# sensor_003.net
KiCad netlist of a schematic drawn in EAGLE
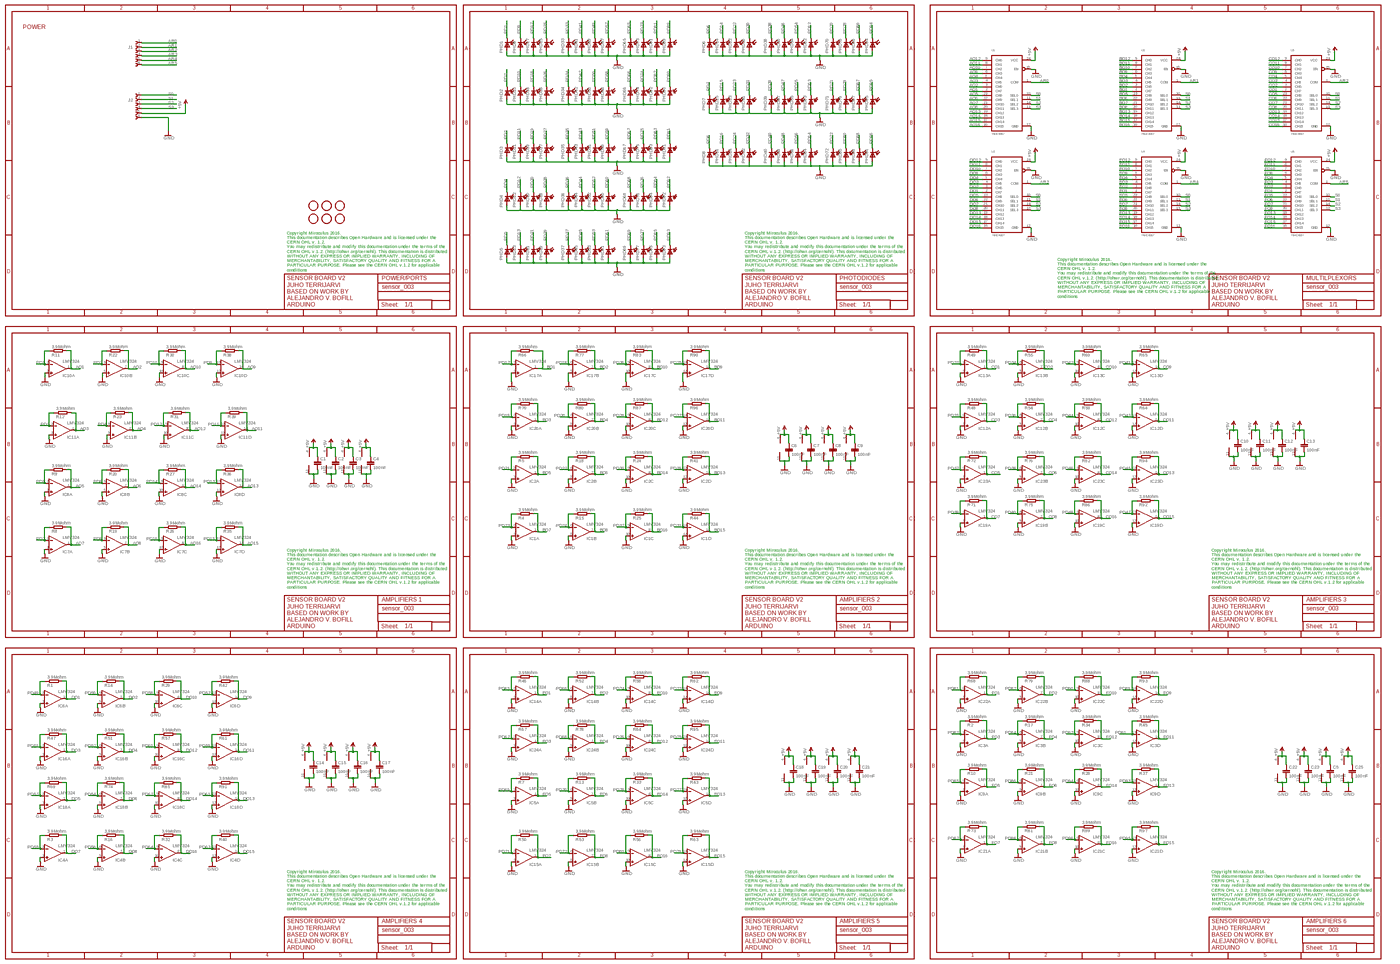
[diagram p0: schematic, sheet 1, overview]
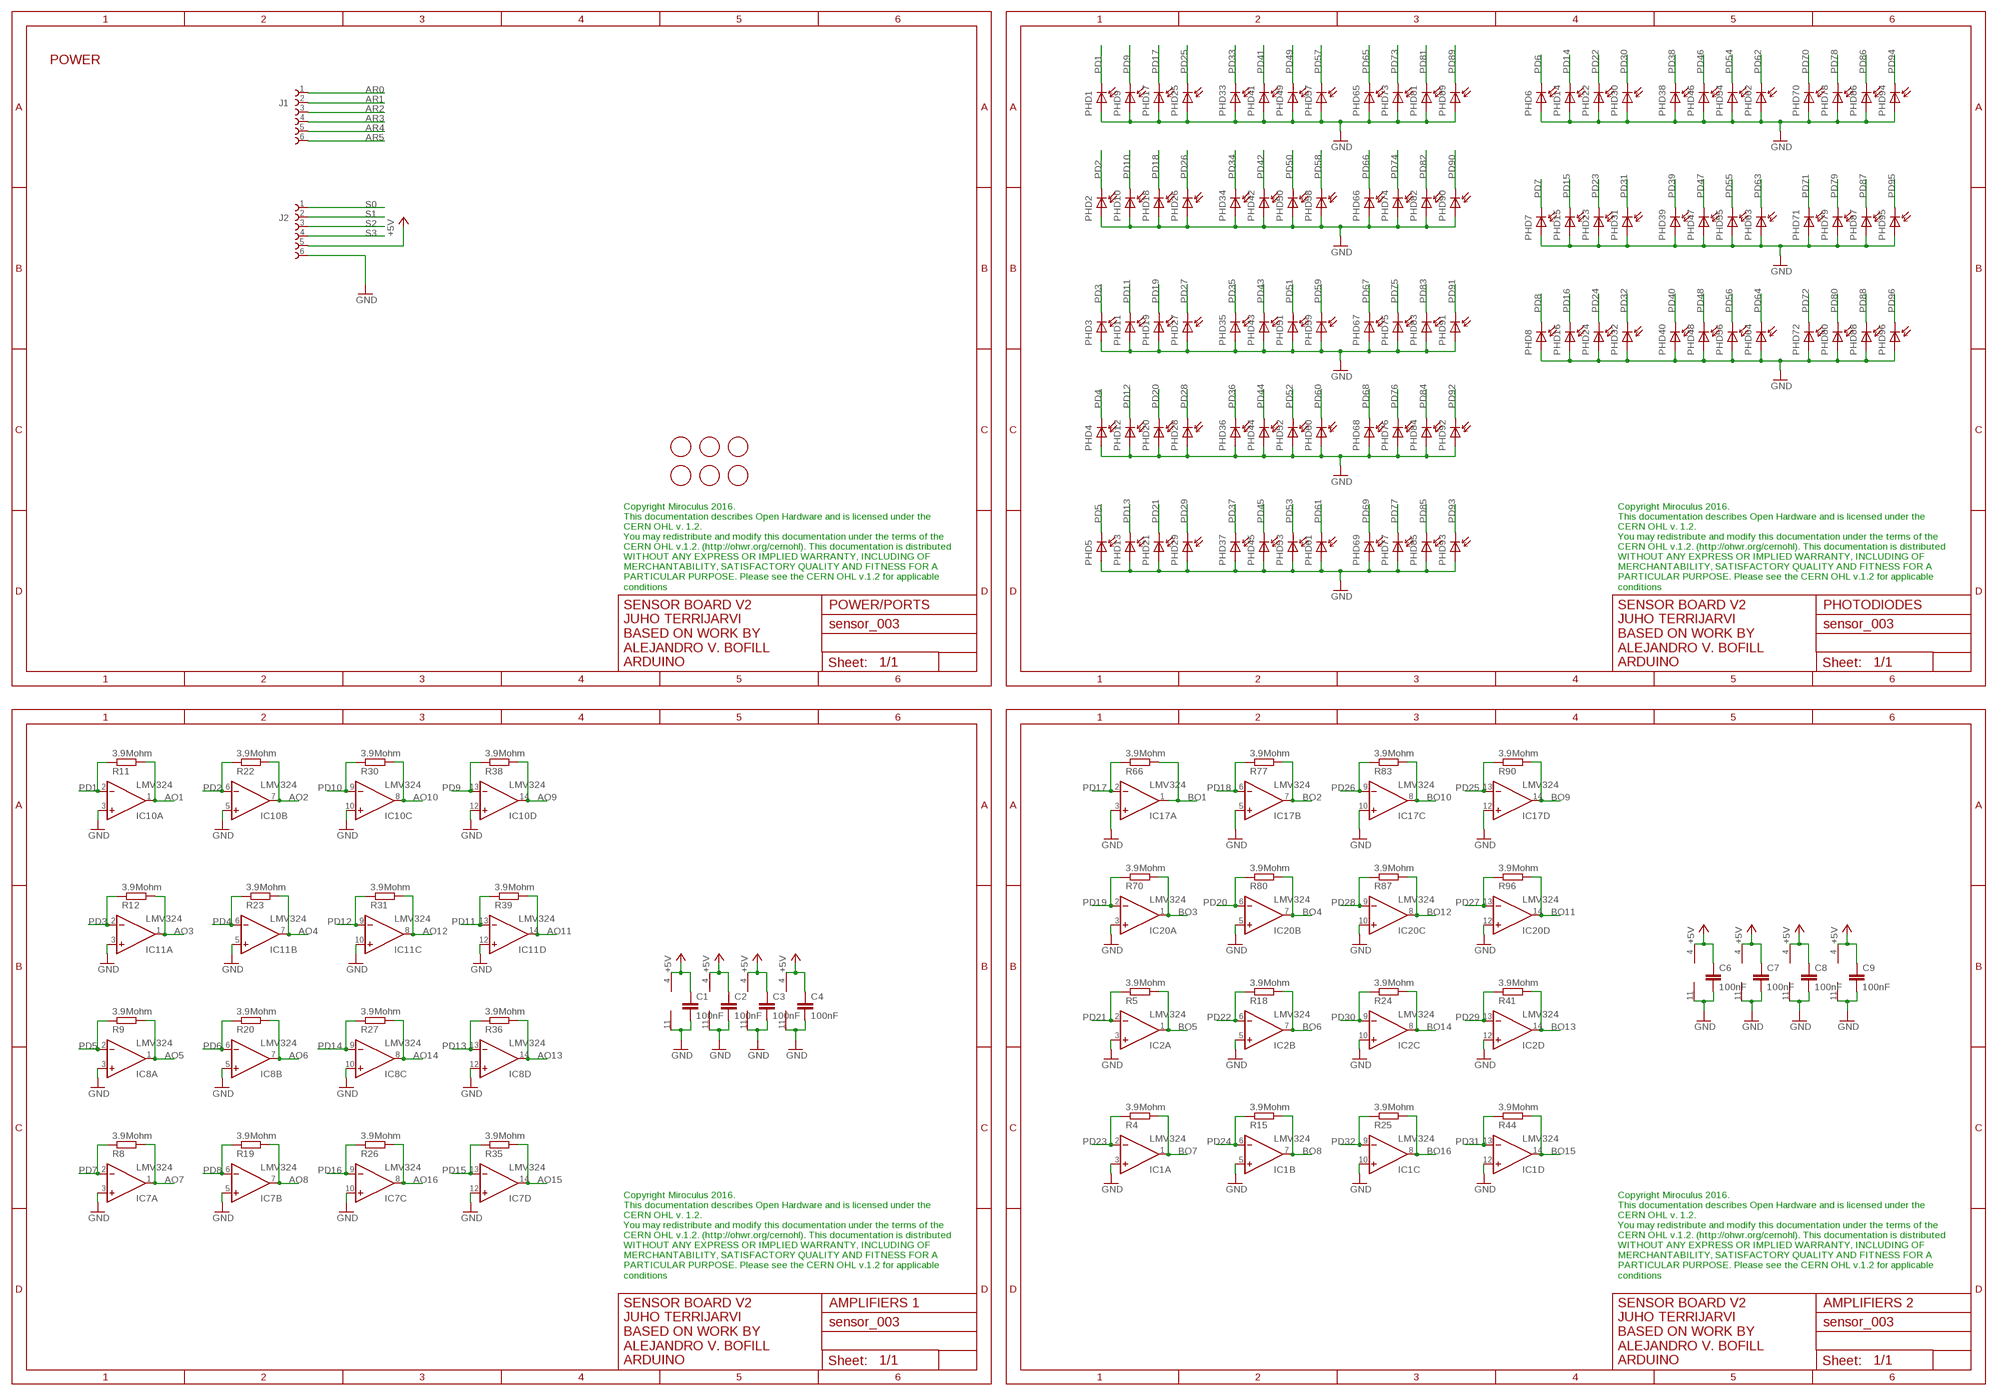
[diagram p1: schematic, sheet 1, part 1 of 4]
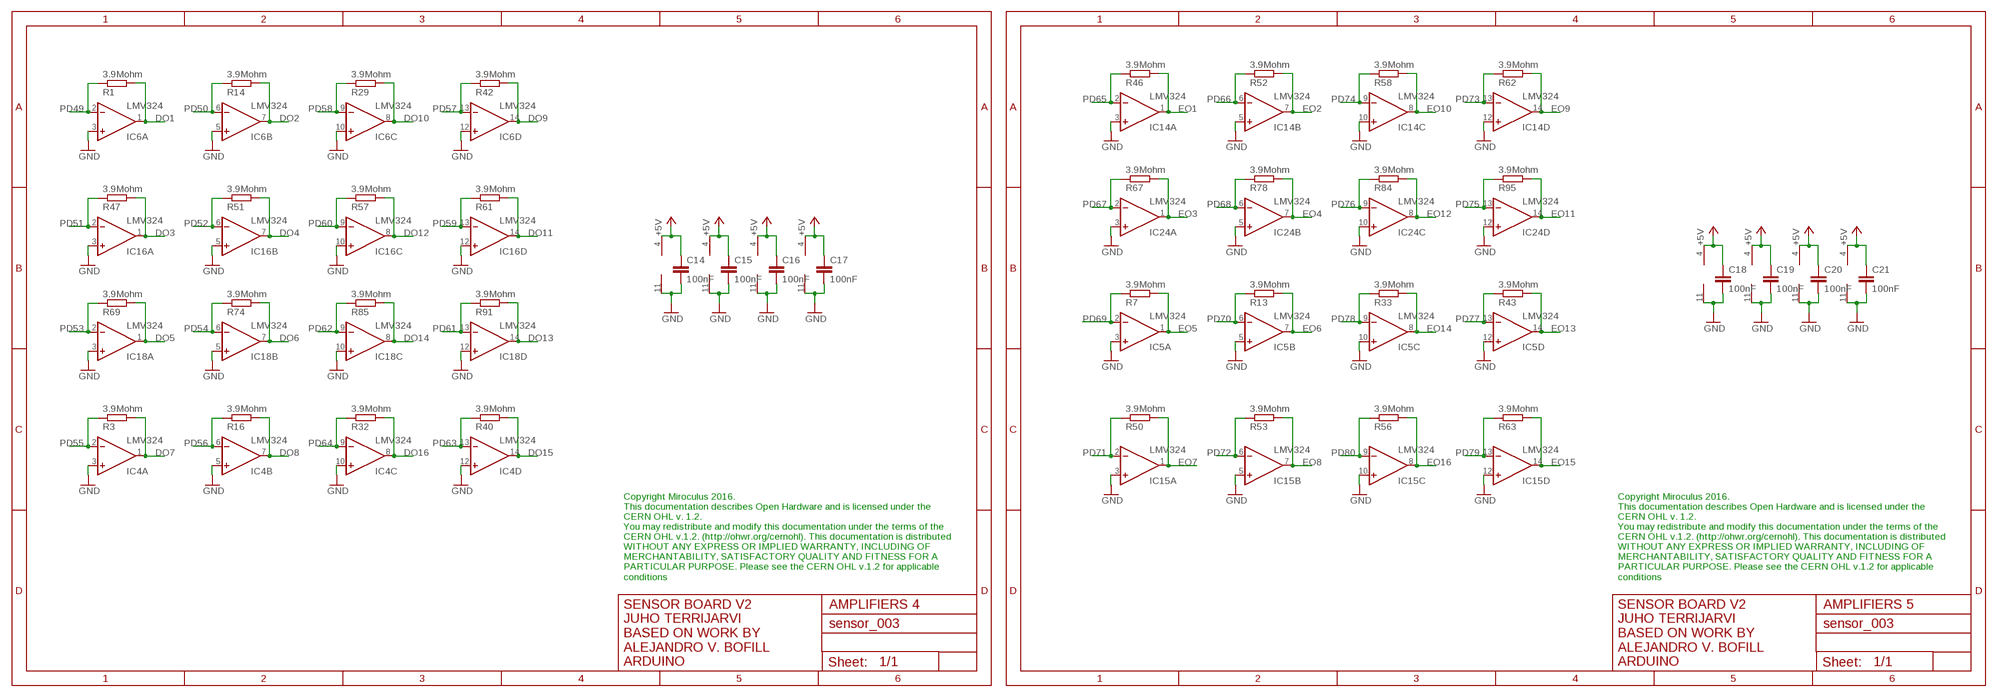
[diagram p2: schematic, sheet 1, part 2 of 4]
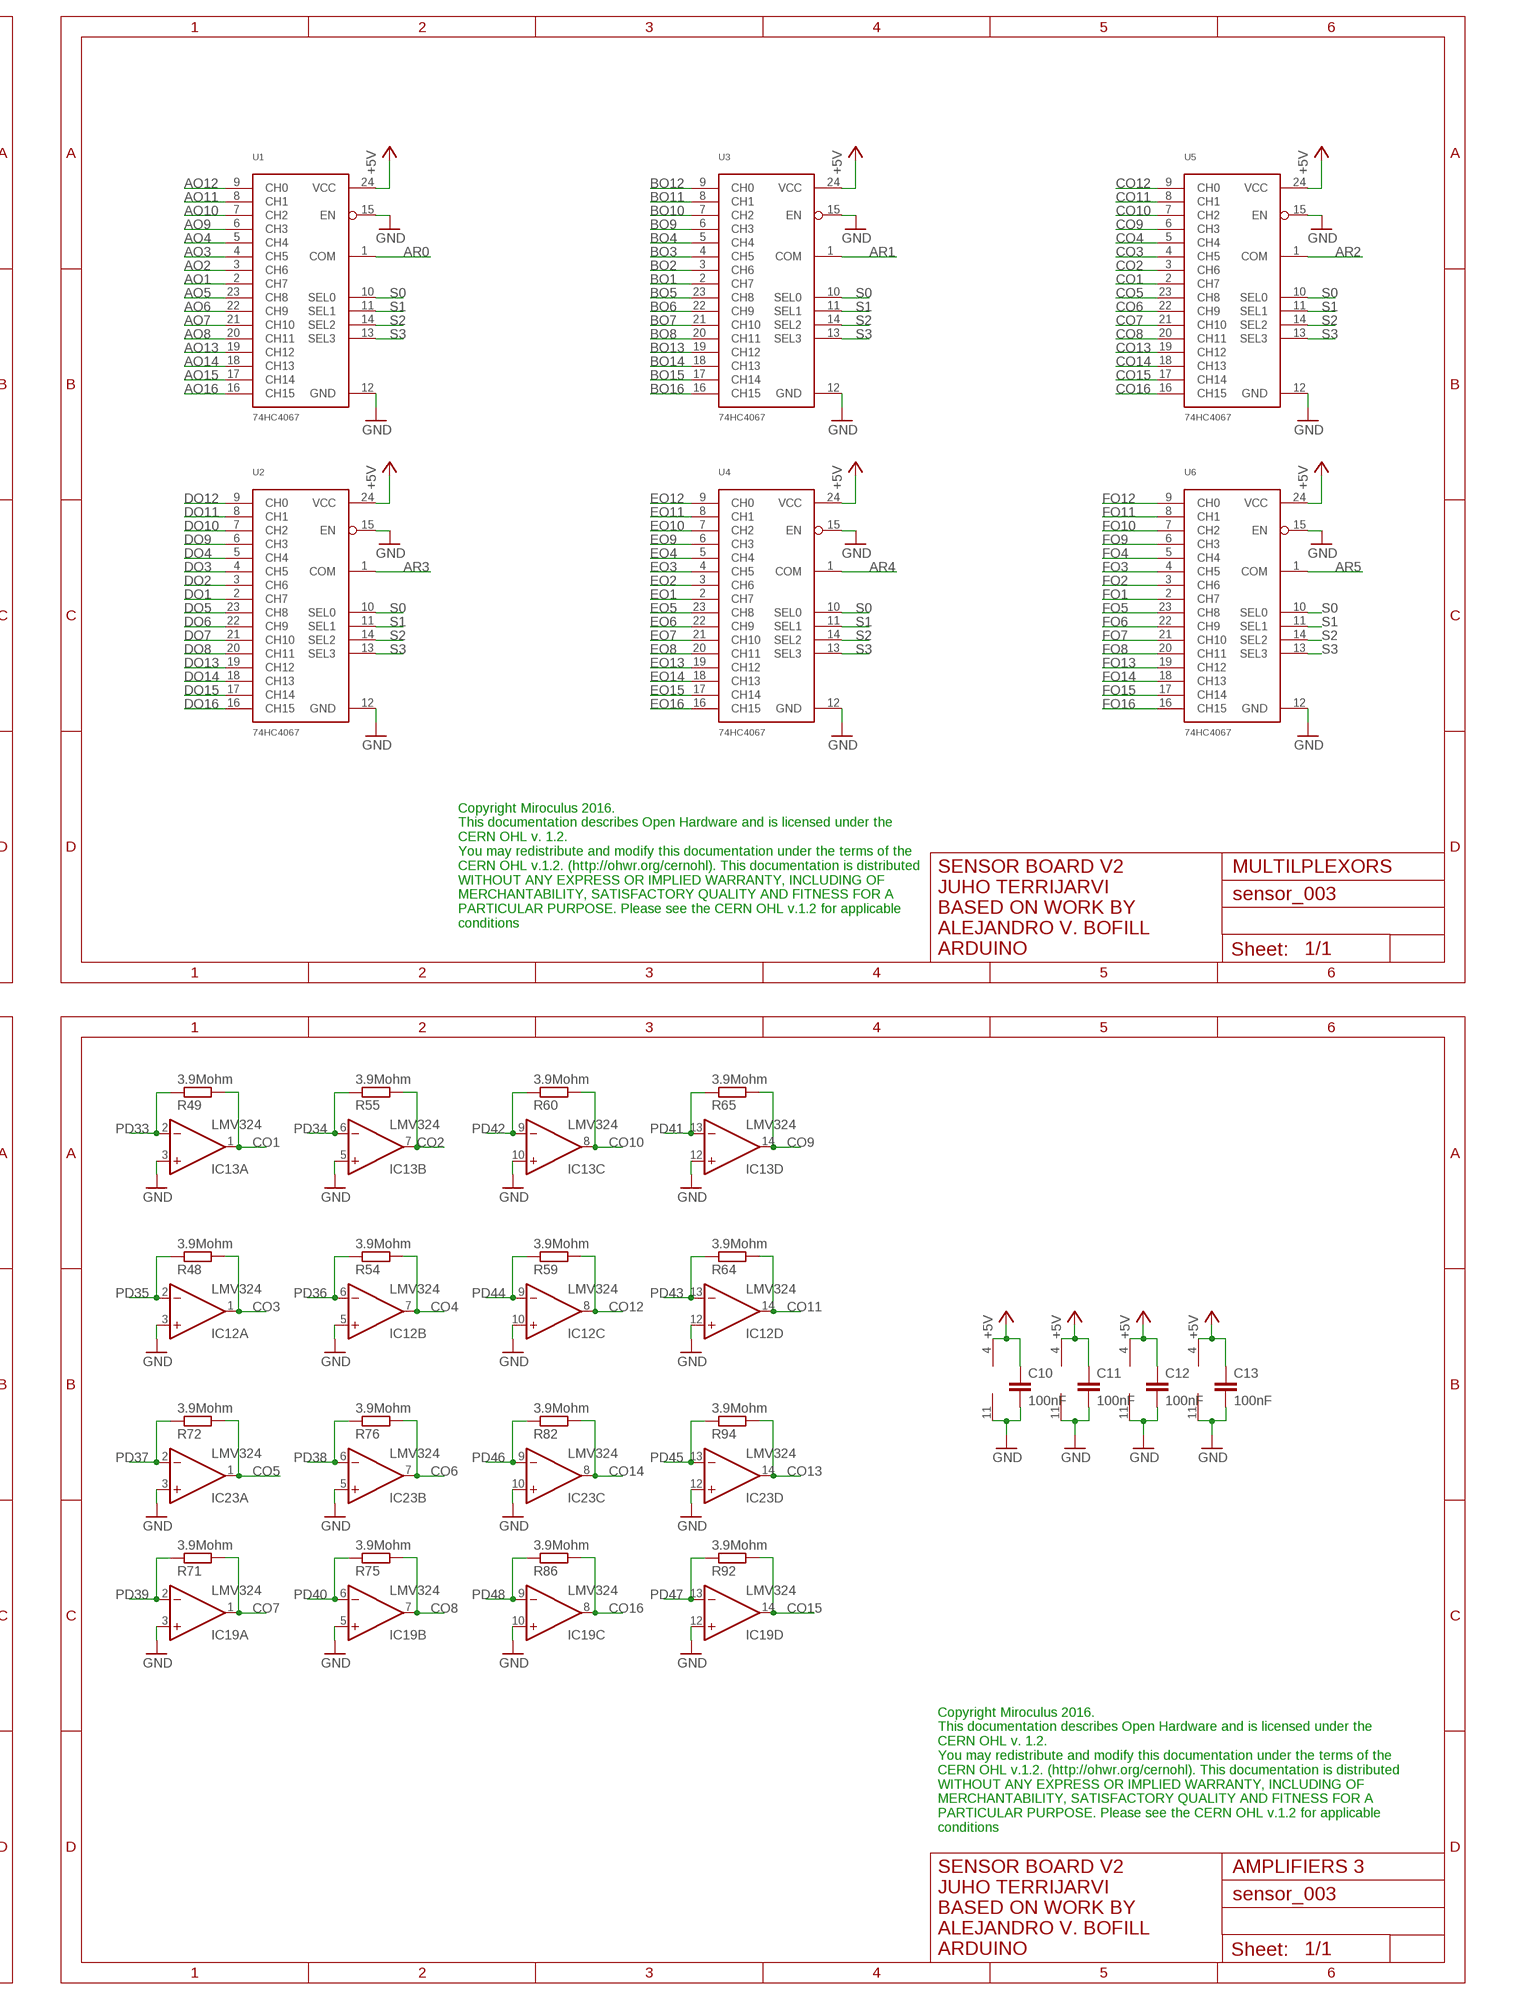
[diagram p3: schematic, sheet 1, part 3 of 4]
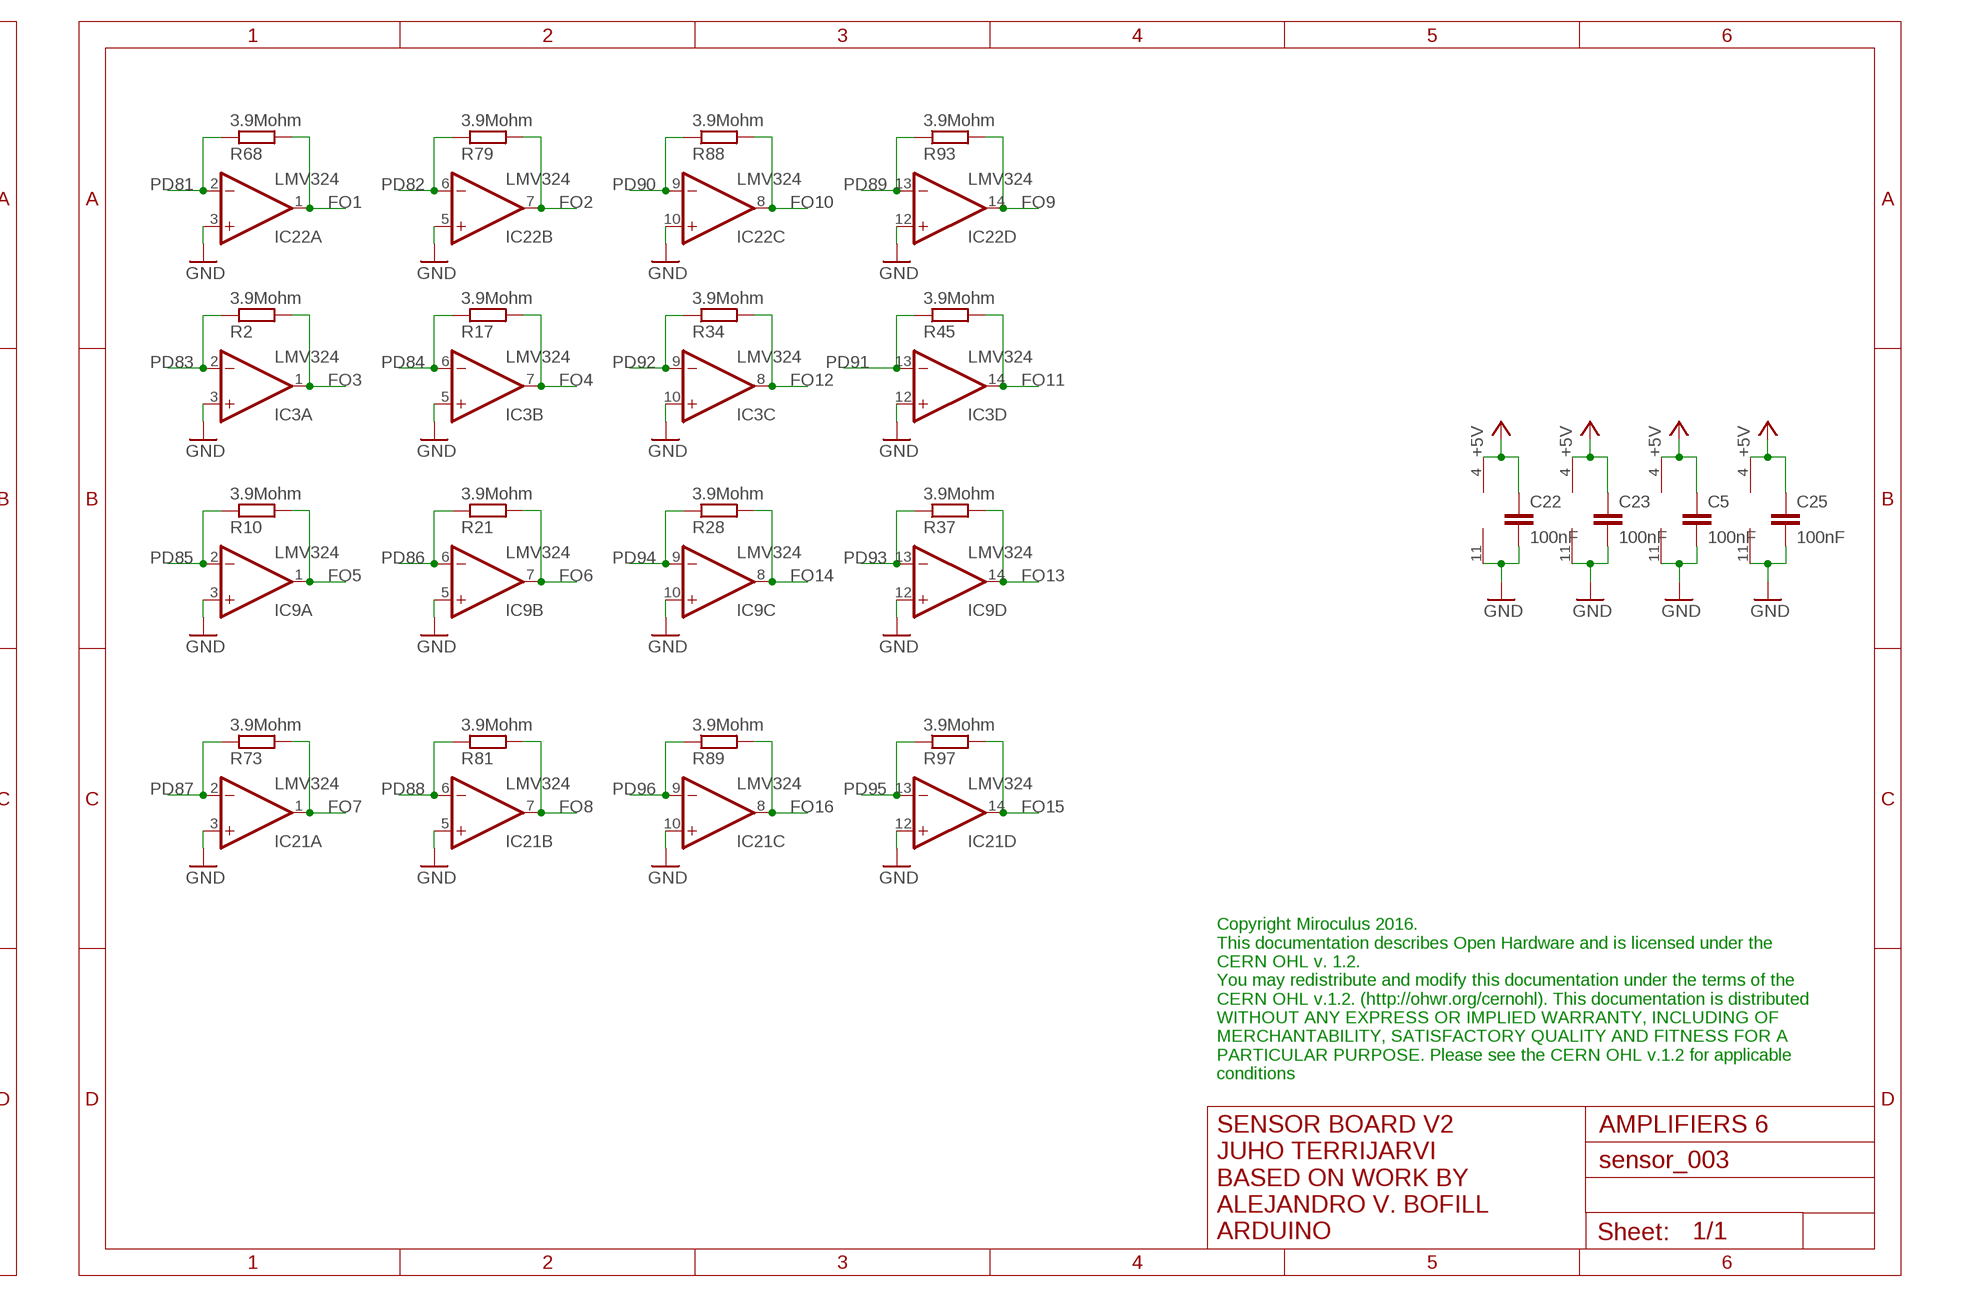
[diagram p4: schematic, sheet 1, part 4 of 4]

(export (version "E")
  (design (tool "Eeschema 10.0.6"))
  (components
    (comp (ref "C1")
      (value "100nF")
      (footprint "eagle-import:C0603")
      (libsource (lib "eagle-import") (part "C-EUC0603"))
    )
    (comp (ref "C2")
      (value "100nF")
      (footprint "eagle-import:C0603")
      (libsource (lib "eagle-import") (part "C-EUC0603"))
    )
    (comp (ref "C3")
      (value "100nF")
      (footprint "eagle-import:C0603")
      (libsource (lib "eagle-import") (part "C-EUC0603"))
    )
    (comp (ref "C4")
      (value "100nF")
      (footprint "eagle-import:C0603")
      (libsource (lib "eagle-import") (part "C-EUC0603"))
    )
    (comp (ref "C5")
      (value "100nF")
      (footprint "eagle-import:C0603")
      (libsource (lib "eagle-import") (part "C-EUC0603"))
    )
    (comp (ref "C6")
      (value "100nF")
      (footprint "eagle-import:C0603")
      (libsource (lib "eagle-import") (part "C-EUC0603"))
    )
    (comp (ref "C7")
      (value "100nF")
      (footprint "eagle-import:C0603")
      (libsource (lib "eagle-import") (part "C-EUC0603"))
    )
    (comp (ref "C8")
      (value "100nF")
      (footprint "eagle-import:C0603")
      (libsource (lib "eagle-import") (part "C-EUC0603"))
    )
    (comp (ref "C9")
      (value "100nF")
      (footprint "eagle-import:C0603")
      (libsource (lib "eagle-import") (part "C-EUC0603"))
    )
    (comp (ref "C10")
      (value "100nF")
      (footprint "eagle-import:C0603")
      (libsource (lib "eagle-import") (part "C-EUC0603"))
    )
    (comp (ref "C11")
      (value "100nF")
      (footprint "eagle-import:C0603")
      (libsource (lib "eagle-import") (part "C-EUC0603"))
    )
    (comp (ref "C12")
      (value "100nF")
      (footprint "eagle-import:C0603")
      (libsource (lib "eagle-import") (part "C-EUC0603"))
    )
    (comp (ref "C13")
      (value "100nF")
      (footprint "eagle-import:C0603")
      (libsource (lib "eagle-import") (part "C-EUC0603"))
    )
    (comp (ref "C14")
      (value "100nF")
      (footprint "eagle-import:C0603")
      (libsource (lib "eagle-import") (part "C-EUC0603"))
    )
    (comp (ref "C15")
      (value "100nF")
      (footprint "eagle-import:C0603")
      (libsource (lib "eagle-import") (part "C-EUC0603"))
    )
    (comp (ref "C16")
      (value "100nF")
      (footprint "eagle-import:C0603")
      (libsource (lib "eagle-import") (part "C-EUC0603"))
    )
    (comp (ref "C17")
      (value "100nF")
      (footprint "eagle-import:C0603")
      (libsource (lib "eagle-import") (part "C-EUC0603"))
    )
    (comp (ref "C18")
      (value "100nF")
      (footprint "eagle-import:C0603")
      (libsource (lib "eagle-import") (part "C-EUC0603"))
    )
    (comp (ref "C19")
      (value "100nF")
      (footprint "eagle-import:C0603")
      (libsource (lib "eagle-import") (part "C-EUC0603"))
    )
    (comp (ref "C20")
      (value "100nF")
      (footprint "eagle-import:C0603")
      (libsource (lib "eagle-import") (part "C-EUC0603"))
    )
    (comp (ref "C21")
      (value "100nF")
      (footprint "eagle-import:C0603")
      (libsource (lib "eagle-import") (part "C-EUC0603"))
    )
    (comp (ref "C22")
      (value "100nF")
      (footprint "eagle-import:C0603")
      (libsource (lib "eagle-import") (part "C-EUC0603"))
    )
    (comp (ref "C23")
      (value "100nF")
      (footprint "eagle-import:C0603")
      (libsource (lib "eagle-import") (part "C-EUC0603"))
    )
    (comp (ref "C25")
      (value "100nF")
      (footprint "eagle-import:C0603")
      (libsource (lib "eagle-import") (part "C-EUC0603"))
    )
    (comp (ref "FD1")
      (value "FIDUCIALMOUNT")
      (footprint "eagle-import:FIDUCIA-MOUNT")
      (libsource (lib "eagle-import") (part "FIDUCIALMOUNT"))
    )
    (comp (ref "FD2")
      (value "FIDUCIALMOUNT")
      (footprint "eagle-import:FIDUCIA-MOUNT")
      (libsource (lib "eagle-import") (part "FIDUCIALMOUNT"))
    )
    (comp (ref "FD3")
      (value "FIDUCIALMOUNT")
      (footprint "eagle-import:FIDUCIA-MOUNT")
      (libsource (lib "eagle-import") (part "FIDUCIALMOUNT"))
    )
    (comp (ref "FD4")
      (value "FIDUCIALMOUNT")
      (footprint "eagle-import:FIDUCIA-MOUNT")
      (libsource (lib "eagle-import") (part "FIDUCIALMOUNT"))
    )
    (comp (ref "FD5")
      (value "FIDUCIALMOUNT")
      (footprint "eagle-import:FIDUCIA-MOUNT")
      (libsource (lib "eagle-import") (part "FIDUCIALMOUNT"))
    )
    (comp (ref "FD6")
      (value "FIDUCIALMOUNT")
      (footprint "eagle-import:FIDUCIA-MOUNT")
      (libsource (lib "eagle-import") (part "FIDUCIALMOUNT"))
    )
    (comp (ref "IC1")
      (value "LMV324")
      (footprint "eagle-import:SO14")
      (libsource (lib "eagle-import") (part "TL074D"))
    )
    (comp (ref "IC2")
      (value "LMV324")
      (footprint "eagle-import:SO14")
      (libsource (lib "eagle-import") (part "TL074D"))
    )
    (comp (ref "IC3")
      (value "LMV324")
      (footprint "eagle-import:SO14")
      (libsource (lib "eagle-import") (part "TL074D"))
    )
    (comp (ref "IC4")
      (value "LMV324")
      (footprint "eagle-import:SO14")
      (libsource (lib "eagle-import") (part "TL074D"))
    )
    (comp (ref "IC5")
      (value "LMV324")
      (footprint "eagle-import:SO14")
      (libsource (lib "eagle-import") (part "TL074D"))
    )
    (comp (ref "IC6")
      (value "LMV324")
      (footprint "eagle-import:SO14")
      (libsource (lib "eagle-import") (part "TL074D"))
    )
    (comp (ref "IC7")
      (value "LMV324")
      (footprint "eagle-import:SO14")
      (libsource (lib "eagle-import") (part "TL074D"))
    )
    (comp (ref "IC8")
      (value "LMV324")
      (footprint "eagle-import:SO14")
      (libsource (lib "eagle-import") (part "TL074D"))
    )
    (comp (ref "IC9")
      (value "LMV324")
      (footprint "eagle-import:SO14")
      (libsource (lib "eagle-import") (part "TL074D"))
    )
    (comp (ref "IC10")
      (value "LMV324")
      (footprint "eagle-import:SO14")
      (libsource (lib "eagle-import") (part "TL074D"))
    )
    (comp (ref "IC11")
      (value "LMV324")
      (footprint "eagle-import:SO14")
      (libsource (lib "eagle-import") (part "TL074D"))
    )
    (comp (ref "IC12")
      (value "LMV324")
      (footprint "eagle-import:SO14")
      (libsource (lib "eagle-import") (part "TL074D"))
    )
    (comp (ref "IC13")
      (value "LMV324")
      (footprint "eagle-import:SO14")
      (libsource (lib "eagle-import") (part "TL074D"))
    )
    (comp (ref "IC14")
      (value "LMV324")
      (footprint "eagle-import:SO14")
      (libsource (lib "eagle-import") (part "TL074D"))
    )
    (comp (ref "IC15")
      (value "LMV324")
      (footprint "eagle-import:SO14")
      (libsource (lib "eagle-import") (part "TL074D"))
    )
    (comp (ref "IC16")
      (value "LMV324")
      (footprint "eagle-import:SO14")
      (libsource (lib "eagle-import") (part "TL074D"))
    )
    (comp (ref "IC17")
      (value "LMV324")
      (footprint "eagle-import:SO14")
      (libsource (lib "eagle-import") (part "TL074D"))
    )
    (comp (ref "IC18")
      (value "LMV324")
      (footprint "eagle-import:SO14")
      (libsource (lib "eagle-import") (part "TL074D"))
    )
    (comp (ref "IC19")
      (value "LMV324")
      (footprint "eagle-import:SO14")
      (libsource (lib "eagle-import") (part "TL074D"))
    )
    (comp (ref "IC20")
      (value "LMV324")
      (footprint "eagle-import:SO14")
      (libsource (lib "eagle-import") (part "TL074D"))
    )
    (comp (ref "IC21")
      (value "LMV324")
      (footprint "eagle-import:SO14")
      (libsource (lib "eagle-import") (part "TL074D"))
    )
    (comp (ref "IC22")
      (value "LMV324")
      (footprint "eagle-import:SO14")
      (libsource (lib "eagle-import") (part "TL074D"))
    )
    (comp (ref "IC23")
      (value "LMV324")
      (footprint "eagle-import:SO14")
      (libsource (lib "eagle-import") (part "TL074D"))
    )
    (comp (ref "IC24")
      (value "LMV324")
      (footprint "eagle-import:SO14")
      (libsource (lib "eagle-import") (part "TL074D"))
    )
    (comp (ref "J1")
      (value "68710614522")
      (footprint "eagle-import:68710614522")
      (libsource (lib "eagle-import") (part "68710614522"))
    )
    (comp (ref "J2")
      (value "68710614522")
      (footprint "eagle-import:68710614522")
      (libsource (lib "eagle-import") (part "68710614522"))
    )
    (comp (ref "PHD1")
      (value "CLS15-22C/L213G/TR8")
      (footprint "eagle-import:PD_0.2")
      (libsource (lib "eagle-import") (part "PD_0.2"))
    )
    (comp (ref "PHD2")
      (value "CLS15-22C/L213G/TR8")
      (footprint "eagle-import:PD_0.2")
      (libsource (lib "eagle-import") (part "PD_0.2"))
    )
    (comp (ref "PHD3")
      (value "CLS15-22C/L213G/TR8")
      (footprint "eagle-import:PD_0.2")
      (libsource (lib "eagle-import") (part "PD_0.2"))
    )
    (comp (ref "PHD4")
      (value "CLS15-22C/L213G/TR8")
      (footprint "eagle-import:PD_0.2")
      (libsource (lib "eagle-import") (part "PD_0.2"))
    )
    (comp (ref "PHD5")
      (value "CLS15-22C/L213G/TR8")
      (footprint "eagle-import:PD_0.2")
      (libsource (lib "eagle-import") (part "PD_0.2"))
    )
    (comp (ref "PHD6")
      (value "CLS15-22C/L213G/TR8")
      (footprint "eagle-import:PD_0.2")
      (libsource (lib "eagle-import") (part "PD_0.2"))
    )
    (comp (ref "PHD7")
      (value "CLS15-22C/L213G/TR8")
      (footprint "eagle-import:PD_0.2")
      (libsource (lib "eagle-import") (part "PD_0.2"))
    )
    (comp (ref "PHD8")
      (value "CLS15-22C/L213G/TR8")
      (footprint "eagle-import:PD_0.2")
      (libsource (lib "eagle-import") (part "PD_0.2"))
    )
    (comp (ref "PHD9")
      (value "CLS15-22C/L213G/TR8")
      (footprint "eagle-import:PD_0.2")
      (libsource (lib "eagle-import") (part "PD_0.2"))
    )
    (comp (ref "PHD10")
      (value "CLS15-22C/L213G/TR8")
      (footprint "eagle-import:PD_0.2")
      (libsource (lib "eagle-import") (part "PD_0.2"))
    )
    (comp (ref "PHD11")
      (value "CLS15-22C/L213G/TR8")
      (footprint "eagle-import:PD_0.2")
      (libsource (lib "eagle-import") (part "PD_0.2"))
    )
    (comp (ref "PHD12")
      (value "CLS15-22C/L213G/TR8")
      (footprint "eagle-import:PD_0.2")
      (libsource (lib "eagle-import") (part "PD_0.2"))
    )
    (comp (ref "PHD13")
      (value "CLS15-22C/L213G/TR8")
      (footprint "eagle-import:PD_0.2")
      (libsource (lib "eagle-import") (part "PD_0.2"))
    )
    (comp (ref "PHD14")
      (value "CLS15-22C/L213G/TR8")
      (footprint "eagle-import:PD_0.2")
      (libsource (lib "eagle-import") (part "PD_0.2"))
    )
    (comp (ref "PHD15")
      (value "CLS15-22C/L213G/TR8")
      (footprint "eagle-import:PD_0.2")
      (libsource (lib "eagle-import") (part "PD_0.2"))
    )
    (comp (ref "PHD16")
      (value "CLS15-22C/L213G/TR8")
      (footprint "eagle-import:PD_0.2")
      (libsource (lib "eagle-import") (part "PD_0.2"))
    )
    (comp (ref "PHD17")
      (value "CLS15-22C/L213G/TR8")
      (footprint "eagle-import:PD_0.2")
      (libsource (lib "eagle-import") (part "PD_0.2"))
    )
    (comp (ref "PHD18")
      (value "CLS15-22C/L213G/TR8")
      (footprint "eagle-import:PD_0.2")
      (libsource (lib "eagle-import") (part "PD_0.2"))
    )
    (comp (ref "PHD19")
      (value "CLS15-22C/L213G/TR8")
      (footprint "eagle-import:PD_0.2")
      (libsource (lib "eagle-import") (part "PD_0.2"))
    )
    (comp (ref "PHD20")
      (value "CLS15-22C/L213G/TR8")
      (footprint "eagle-import:PD_0.2")
      (libsource (lib "eagle-import") (part "PD_0.2"))
    )
    (comp (ref "PHD21")
      (value "CLS15-22C/L213G/TR8")
      (footprint "eagle-import:PD_0.2")
      (libsource (lib "eagle-import") (part "PD_0.2"))
    )
    (comp (ref "PHD22")
      (value "CLS15-22C/L213G/TR8")
      (footprint "eagle-import:PD_0.2")
      (libsource (lib "eagle-import") (part "PD_0.2"))
    )
    (comp (ref "PHD23")
      (value "CLS15-22C/L213G/TR8")
      (footprint "eagle-import:PD_0.2")
      (libsource (lib "eagle-import") (part "PD_0.2"))
    )
    (comp (ref "PHD24")
      (value "CLS15-22C/L213G/TR8")
      (footprint "eagle-import:PD_0.2")
      (libsource (lib "eagle-import") (part "PD_0.2"))
    )
    (comp (ref "PHD25")
      (value "CLS15-22C/L213G/TR8")
      (footprint "eagle-import:PD_0.2")
      (libsource (lib "eagle-import") (part "PD_0.2"))
    )
    (comp (ref "PHD26")
      (value "CLS15-22C/L213G/TR8")
      (footprint "eagle-import:PD_0.2")
      (libsource (lib "eagle-import") (part "PD_0.2"))
    )
    (comp (ref "PHD27")
      (value "CLS15-22C/L213G/TR8")
      (footprint "eagle-import:PD_0.2")
      (libsource (lib "eagle-import") (part "PD_0.2"))
    )
    (comp (ref "PHD28")
      (value "CLS15-22C/L213G/TR8")
      (footprint "eagle-import:PD_0.2")
      (libsource (lib "eagle-import") (part "PD_0.2"))
    )
    (comp (ref "PHD29")
      (value "CLS15-22C/L213G/TR8")
      (footprint "eagle-import:PD_0.2")
      (libsource (lib "eagle-import") (part "PD_0.2"))
    )
    (comp (ref "PHD30")
      (value "CLS15-22C/L213G/TR8")
      (footprint "eagle-import:PD_0.2")
      (libsource (lib "eagle-import") (part "PD_0.2"))
    )
    (comp (ref "PHD31")
      (value "CLS15-22C/L213G/TR8")
      (footprint "eagle-import:PD_0.2")
      (libsource (lib "eagle-import") (part "PD_0.2"))
    )
    (comp (ref "PHD32")
      (value "CLS15-22C/L213G/TR8")
      (footprint "eagle-import:PD_0.2")
      (libsource (lib "eagle-import") (part "PD_0.2"))
    )
    (comp (ref "PHD33")
      (value "CLS15-22C/L213G/TR8")
      (footprint "eagle-import:PD_0.2")
      (libsource (lib "eagle-import") (part "PD_0.2"))
    )
    (comp (ref "PHD34")
      (value "CLS15-22C/L213G/TR8")
      (footprint "eagle-import:PD_0.2")
      (libsource (lib "eagle-import") (part "PD_0.2"))
    )
    (comp (ref "PHD35")
      (value "CLS15-22C/L213G/TR8")
      (footprint "eagle-import:PD_0.2")
      (libsource (lib "eagle-import") (part "PD_0.2"))
    )
    (comp (ref "PHD36")
      (value "CLS15-22C/L213G/TR8")
      (footprint "eagle-import:PD_0.2")
      (libsource (lib "eagle-import") (part "PD_0.2"))
    )
    (comp (ref "PHD37")
      (value "CLS15-22C/L213G/TR8")
      (footprint "eagle-import:PD_0.2")
      (libsource (lib "eagle-import") (part "PD_0.2"))
    )
    (comp (ref "PHD38")
      (value "CLS15-22C/L213G/TR8")
      (footprint "eagle-import:PD_0.2")
      (libsource (lib "eagle-import") (part "PD_0.2"))
    )
    (comp (ref "PHD39")
      (value "CLS15-22C/L213G/TR8")
      (footprint "eagle-import:PD_0.2")
      (libsource (lib "eagle-import") (part "PD_0.2"))
    )
    (comp (ref "PHD40")
      (value "CLS15-22C/L213G/TR8")
      (footprint "eagle-import:PD_0.2")
      (libsource (lib "eagle-import") (part "PD_0.2"))
    )
    (comp (ref "PHD41")
      (value "CLS15-22C/L213G/TR8")
      (footprint "eagle-import:PD_0.2")
      (libsource (lib "eagle-import") (part "PD_0.2"))
    )
    (comp (ref "PHD42")
      (value "CLS15-22C/L213G/TR8")
      (footprint "eagle-import:PD_0.2")
      (libsource (lib "eagle-import") (part "PD_0.2"))
    )
    (comp (ref "PHD43")
      (value "CLS15-22C/L213G/TR8")
      (footprint "eagle-import:PD_0.2")
      (libsource (lib "eagle-import") (part "PD_0.2"))
    )
    (comp (ref "PHD44")
      (value "CLS15-22C/L213G/TR8")
      (footprint "eagle-import:PD_0.2")
      (libsource (lib "eagle-import") (part "PD_0.2"))
    )
    (comp (ref "PHD45")
      (value "CLS15-22C/L213G/TR8")
      (footprint "eagle-import:PD_0.2")
      (libsource (lib "eagle-import") (part "PD_0.2"))
    )
    (comp (ref "PHD46")
      (value "CLS15-22C/L213G/TR8")
      (footprint "eagle-import:PD_0.2")
      (libsource (lib "eagle-import") (part "PD_0.2"))
    )
    (comp (ref "PHD47")
      (value "CLS15-22C/L213G/TR8")
      (footprint "eagle-import:PD_0.2")
      (libsource (lib "eagle-import") (part "PD_0.2"))
    )
    (comp (ref "PHD48")
      (value "CLS15-22C/L213G/TR8")
      (footprint "eagle-import:PD_0.2")
      (libsource (lib "eagle-import") (part "PD_0.2"))
    )
    (comp (ref "PHD49")
      (value "CLS15-22C/L213G/TR8")
      (footprint "eagle-import:PD_0.2")
      (libsource (lib "eagle-import") (part "PD_0.2"))
    )
    (comp (ref "PHD50")
      (value "CLS15-22C/L213G/TR8")
      (footprint "eagle-import:PD_0.2")
      (libsource (lib "eagle-import") (part "PD_0.2"))
    )
    (comp (ref "PHD51")
      (value "CLS15-22C/L213G/TR8")
      (footprint "eagle-import:PD_0.2")
      (libsource (lib "eagle-import") (part "PD_0.2"))
    )
    (comp (ref "PHD52")
      (value "CLS15-22C/L213G/TR8")
      (footprint "eagle-import:PD_0.2")
      (libsource (lib "eagle-import") (part "PD_0.2"))
    )
    (comp (ref "PHD53")
      (value "CLS15-22C/L213G/TR8")
      (footprint "eagle-import:PD_0.2")
      (libsource (lib "eagle-import") (part "PD_0.2"))
    )
    (comp (ref "PHD54")
      (value "CLS15-22C/L213G/TR8")
      (footprint "eagle-import:PD_0.2")
      (libsource (lib "eagle-import") (part "PD_0.2"))
    )
    (comp (ref "PHD55")
      (value "CLS15-22C/L213G/TR8")
      (footprint "eagle-import:PD_0.2")
      (libsource (lib "eagle-import") (part "PD_0.2"))
    )
    (comp (ref "PHD56")
      (value "CLS15-22C/L213G/TR8")
      (footprint "eagle-import:PD_0.2")
      (libsource (lib "eagle-import") (part "PD_0.2"))
    )
    (comp (ref "PHD57")
      (value "CLS15-22C/L213G/TR8")
      (footprint "eagle-import:PD_0.2")
      (libsource (lib "eagle-import") (part "PD_0.2"))
    )
    (comp (ref "PHD58")
      (value "CLS15-22C/L213G/TR8")
      (footprint "eagle-import:PD_0.2")
      (libsource (lib "eagle-import") (part "PD_0.2"))
    )
    (comp (ref "PHD59")
      (value "CLS15-22C/L213G/TR8")
      (footprint "eagle-import:PD_0.2")
      (libsource (lib "eagle-import") (part "PD_0.2"))
    )
    (comp (ref "PHD60")
      (value "CLS15-22C/L213G/TR8")
      (footprint "eagle-import:PD_0.2")
      (libsource (lib "eagle-import") (part "PD_0.2"))
    )
    (comp (ref "PHD61")
      (value "CLS15-22C/L213G/TR8")
      (footprint "eagle-import:PD_0.2")
      (libsource (lib "eagle-import") (part "PD_0.2"))
    )
    (comp (ref "PHD62")
      (value "CLS15-22C/L213G/TR8")
      (footprint "eagle-import:PD_0.2")
      (libsource (lib "eagle-import") (part "PD_0.2"))
    )
    (comp (ref "PHD63")
      (value "CLS15-22C/L213G/TR8")
      (footprint "eagle-import:PD_0.2")
      (libsource (lib "eagle-import") (part "PD_0.2"))
    )
    (comp (ref "PHD64")
      (value "CLS15-22C/L213G/TR8")
      (footprint "eagle-import:PD_0.2")
      (libsource (lib "eagle-import") (part "PD_0.2"))
    )
    (comp (ref "PHD65")
      (value "CLS15-22C/L213G/TR8")
      (footprint "eagle-import:PD_0.2")
      (libsource (lib "eagle-import") (part "PD_0.2"))
    )
    (comp (ref "PHD66")
      (value "CLS15-22C/L213G/TR8")
      (footprint "eagle-import:PD_0.2")
      (libsource (lib "eagle-import") (part "PD_0.2"))
    )
    (comp (ref "PHD67")
      (value "CLS15-22C/L213G/TR8")
      (footprint "eagle-import:PD_0.2")
      (libsource (lib "eagle-import") (part "PD_0.2"))
    )
    (comp (ref "PHD68")
      (value "CLS15-22C/L213G/TR8")
      (footprint "eagle-import:PD_0.2")
      (libsource (lib "eagle-import") (part "PD_0.2"))
    )
    (comp (ref "PHD69")
      (value "CLS15-22C/L213G/TR8")
      (footprint "eagle-import:PD_0.2")
      (libsource (lib "eagle-import") (part "PD_0.2"))
    )
    (comp (ref "PHD70")
      (value "CLS15-22C/L213G/TR8")
      (footprint "eagle-import:PD_0.2")
      (libsource (lib "eagle-import") (part "PD_0.2"))
    )
    (comp (ref "PHD71")
      (value "CLS15-22C/L213G/TR8")
      (footprint "eagle-import:PD_0.2")
      (libsource (lib "eagle-import") (part "PD_0.2"))
    )
    (comp (ref "PHD72")
      (value "CLS15-22C/L213G/TR8")
      (footprint "eagle-import:PD_0.2")
      (libsource (lib "eagle-import") (part "PD_0.2"))
    )
    (comp (ref "PHD73")
      (value "CLS15-22C/L213G/TR8")
      (footprint "eagle-import:PD_0.2")
      (libsource (lib "eagle-import") (part "PD_0.2"))
    )
    (comp (ref "PHD74")
      (value "CLS15-22C/L213G/TR8")
      (footprint "eagle-import:PD_0.2")
      (libsource (lib "eagle-import") (part "PD_0.2"))
    )
    (comp (ref "PHD75")
      (value "CLS15-22C/L213G/TR8")
      (footprint "eagle-import:PD_0.2")
      (libsource (lib "eagle-import") (part "PD_0.2"))
    )
    (comp (ref "PHD76")
      (value "CLS15-22C/L213G/TR8")
      (footprint "eagle-import:PD_0.2")
      (libsource (lib "eagle-import") (part "PD_0.2"))
    )
    (comp (ref "PHD77")
      (value "CLS15-22C/L213G/TR8")
      (footprint "eagle-import:PD_0.2")
      (libsource (lib "eagle-import") (part "PD_0.2"))
    )
    (comp (ref "PHD78")
      (value "CLS15-22C/L213G/TR8")
      (footprint "eagle-import:PD_0.2")
      (libsource (lib "eagle-import") (part "PD_0.2"))
    )
    (comp (ref "PHD79")
      (value "CLS15-22C/L213G/TR8")
      (footprint "eagle-import:PD_0.2")
      (libsource (lib "eagle-import") (part "PD_0.2"))
    )
    (comp (ref "PHD80")
      (value "CLS15-22C/L213G/TR8")
      (footprint "eagle-import:PD_0.2")
      (libsource (lib "eagle-import") (part "PD_0.2"))
    )
    (comp (ref "PHD81")
      (value "CLS15-22C/L213G/TR8")
      (footprint "eagle-import:PD_0.2")
      (libsource (lib "eagle-import") (part "PD_0.2"))
    )
    (comp (ref "PHD82")
      (value "CLS15-22C/L213G/TR8")
      (footprint "eagle-import:PD_0.2")
      (libsource (lib "eagle-import") (part "PD_0.2"))
    )
    (comp (ref "PHD83")
      (value "CLS15-22C/L213G/TR8")
      (footprint "eagle-import:PD_0.2")
      (libsource (lib "eagle-import") (part "PD_0.2"))
    )
    (comp (ref "PHD84")
      (value "CLS15-22C/L213G/TR8")
      (footprint "eagle-import:PD_0.2")
      (libsource (lib "eagle-import") (part "PD_0.2"))
    )
    (comp (ref "PHD85")
      (value "CLS15-22C/L213G/TR8")
      (footprint "eagle-import:PD_0.2")
      (libsource (lib "eagle-import") (part "PD_0.2"))
    )
    (comp (ref "PHD86")
      (value "CLS15-22C/L213G/TR8")
      (footprint "eagle-import:PD_0.2")
      (libsource (lib "eagle-import") (part "PD_0.2"))
    )
    (comp (ref "PHD87")
      (value "CLS15-22C/L213G/TR8")
      (footprint "eagle-import:PD_0.2")
      (libsource (lib "eagle-import") (part "PD_0.2"))
    )
    (comp (ref "PHD88")
      (value "CLS15-22C/L213G/TR8")
      (footprint "eagle-import:PD_0.2")
      (libsource (lib "eagle-import") (part "PD_0.2"))
    )
    (comp (ref "PHD89")
      (value "CLS15-22C/L213G/TR8")
      (footprint "eagle-import:PD_0.2")
      (libsource (lib "eagle-import") (part "PD_0.2"))
    )
    (comp (ref "PHD90")
      (value "CLS15-22C/L213G/TR8")
      (footprint "eagle-import:PD_0.2")
      (libsource (lib "eagle-import") (part "PD_0.2"))
    )
    (comp (ref "PHD91")
      (value "CLS15-22C/L213G/TR8")
      (footprint "eagle-import:PD_0.2")
      (libsource (lib "eagle-import") (part "PD_0.2"))
    )
    (comp (ref "PHD92")
      (value "CLS15-22C/L213G/TR8")
      (footprint "eagle-import:PD_0.2")
      (libsource (lib "eagle-import") (part "PD_0.2"))
    )
    (comp (ref "PHD93")
      (value "CLS15-22C/L213G/TR8")
      (footprint "eagle-import:PD_0.2")
      (libsource (lib "eagle-import") (part "PD_0.2"))
    )
    (comp (ref "PHD94")
      (value "CLS15-22C/L213G/TR8")
      (footprint "eagle-import:PD_0.2")
      (libsource (lib "eagle-import") (part "PD_0.2"))
    )
    (comp (ref "PHD95")
      (value "CLS15-22C/L213G/TR8")
      (footprint "eagle-import:PD_0.2")
      (libsource (lib "eagle-import") (part "PD_0.2"))
    )
    (comp (ref "PHD96")
      (value "CLS15-22C/L213G/TR8")
      (footprint "eagle-import:PD_0.2")
      (libsource (lib "eagle-import") (part "PD_0.2"))
    )
    (comp (ref "R1")
      (value "3.9Mohm")
      (footprint "eagle-import:R0603")
      (libsource (lib "eagle-import") (part "R-EU_R0603"))
    )
    (comp (ref "R2")
      (value "3.9Mohm")
      (footprint "eagle-import:R0603")
      (libsource (lib "eagle-import") (part "R-EU_R0603"))
    )
    (comp (ref "R3")
      (value "3.9Mohm")
      (footprint "eagle-import:R0603")
      (libsource (lib "eagle-import") (part "R-EU_R0603"))
    )
    (comp (ref "R4")
      (value "3.9Mohm")
      (footprint "eagle-import:R0603")
      (libsource (lib "eagle-import") (part "R-EU_R0603"))
    )
    (comp (ref "R5")
      (value "3.9Mohm")
      (footprint "eagle-import:R0603")
      (libsource (lib "eagle-import") (part "R-EU_R0603"))
    )
    (comp (ref "R7")
      (value "3.9Mohm")
      (footprint "eagle-import:R0603")
      (libsource (lib "eagle-import") (part "R-EU_R0603"))
    )
    (comp (ref "R8")
      (value "3.9Mohm")
      (footprint "eagle-import:R0603")
      (libsource (lib "eagle-import") (part "R-EU_R0603"))
    )
    (comp (ref "R9")
      (value "3.9Mohm")
      (footprint "eagle-import:R0603")
      (libsource (lib "eagle-import") (part "R-EU_R0603"))
    )
    (comp (ref "R10")
      (value "3.9Mohm")
      (footprint "eagle-import:R0603")
      (libsource (lib "eagle-import") (part "R-EU_R0603"))
    )
    (comp (ref "R11")
      (value "3.9Mohm")
      (footprint "eagle-import:R0603")
      (libsource (lib "eagle-import") (part "R-EU_R0603"))
    )
    (comp (ref "R12")
      (value "3.9Mohm")
      (footprint "eagle-import:R0603")
      (libsource (lib "eagle-import") (part "R-EU_R0603"))
    )
    (comp (ref "R13")
      (value "3.9Mohm")
      (footprint "eagle-import:R0603")
      (libsource (lib "eagle-import") (part "R-EU_R0603"))
    )
    (comp (ref "R14")
      (value "3.9Mohm")
      (footprint "eagle-import:R0603")
      (libsource (lib "eagle-import") (part "R-EU_R0603"))
    )
    (comp (ref "R15")
      (value "3.9Mohm")
      (footprint "eagle-import:R0603")
      (libsource (lib "eagle-import") (part "R-EU_R0603"))
    )
    (comp (ref "R16")
      (value "3.9Mohm")
      (footprint "eagle-import:R0603")
      (libsource (lib "eagle-import") (part "R-EU_R0603"))
    )
    (comp (ref "R17")
      (value "3.9Mohm")
      (footprint "eagle-import:R0603")
      (libsource (lib "eagle-import") (part "R-EU_R0603"))
    )
    (comp (ref "R18")
      (value "3.9Mohm")
      (footprint "eagle-import:R0603")
      (libsource (lib "eagle-import") (part "R-EU_R0603"))
    )
    (comp (ref "R19")
      (value "3.9Mohm")
      (footprint "eagle-import:R0603")
      (libsource (lib "eagle-import") (part "R-EU_R0603"))
    )
    (comp (ref "R20")
      (value "3.9Mohm")
      (footprint "eagle-import:R0603")
      (libsource (lib "eagle-import") (part "R-EU_R0603"))
    )
    (comp (ref "R21")
      (value "3.9Mohm")
      (footprint "eagle-import:R0603")
      (libsource (lib "eagle-import") (part "R-EU_R0603"))
    )
    (comp (ref "R22")
      (value "3.9Mohm")
      (footprint "eagle-import:R0603")
      (libsource (lib "eagle-import") (part "R-EU_R0603"))
    )
    (comp (ref "R23")
      (value "3.9Mohm")
      (footprint "eagle-import:R0603")
      (libsource (lib "eagle-import") (part "R-EU_R0603"))
    )
    (comp (ref "R24")
      (value "3.9Mohm")
      (footprint "eagle-import:R0603")
      (libsource (lib "eagle-import") (part "R-EU_R0603"))
    )
    (comp (ref "R25")
      (value "3.9Mohm")
      (footprint "eagle-import:R0603")
      (libsource (lib "eagle-import") (part "R-EU_R0603"))
    )
    (comp (ref "R26")
      (value "3.9Mohm")
      (footprint "eagle-import:R0603")
      (libsource (lib "eagle-import") (part "R-EU_R0603"))
    )
    (comp (ref "R27")
      (value "3.9Mohm")
      (footprint "eagle-import:R0603")
      (libsource (lib "eagle-import") (part "R-EU_R0603"))
    )
    (comp (ref "R28")
      (value "3.9Mohm")
      (footprint "eagle-import:R0603")
      (libsource (lib "eagle-import") (part "R-EU_R0603"))
    )
    (comp (ref "R29")
      (value "3.9Mohm")
      (footprint "eagle-import:R0603")
      (libsource (lib "eagle-import") (part "R-EU_R0603"))
    )
    (comp (ref "R30")
      (value "3.9Mohm")
      (footprint "eagle-import:R0603")
      (libsource (lib "eagle-import") (part "R-EU_R0603"))
    )
    (comp (ref "R31")
      (value "3.9Mohm")
      (footprint "eagle-import:R0603")
      (libsource (lib "eagle-import") (part "R-EU_R0603"))
    )
    (comp (ref "R32")
      (value "3.9Mohm")
      (footprint "eagle-import:R0603")
      (libsource (lib "eagle-import") (part "R-EU_R0603"))
    )
    (comp (ref "R33")
      (value "3.9Mohm")
      (footprint "eagle-import:R0603")
      (libsource (lib "eagle-import") (part "R-EU_R0603"))
    )
    (comp (ref "R34")
      (value "3.9Mohm")
      (footprint "eagle-import:R0603")
      (libsource (lib "eagle-import") (part "R-EU_R0603"))
    )
    (comp (ref "R35")
      (value "3.9Mohm")
      (footprint "eagle-import:R0603")
      (libsource (lib "eagle-import") (part "R-EU_R0603"))
    )
    (comp (ref "R36")
      (value "3.9Mohm")
      (footprint "eagle-import:R0603")
      (libsource (lib "eagle-import") (part "R-EU_R0603"))
    )
    (comp (ref "R37")
      (value "3.9Mohm")
      (footprint "eagle-import:R0603")
      (libsource (lib "eagle-import") (part "R-EU_R0603"))
    )
    (comp (ref "R38")
      (value "3.9Mohm")
      (footprint "eagle-import:R0603")
      (libsource (lib "eagle-import") (part "R-EU_R0603"))
    )
    (comp (ref "R39")
      (value "3.9Mohm")
      (footprint "eagle-import:R0603")
      (libsource (lib "eagle-import") (part "R-EU_R0603"))
    )
    (comp (ref "R40")
      (value "3.9Mohm")
      (footprint "eagle-import:R0603")
      (libsource (lib "eagle-import") (part "R-EU_R0603"))
    )
    (comp (ref "R41")
      (value "3.9Mohm")
      (footprint "eagle-import:R0603")
      (libsource (lib "eagle-import") (part "R-EU_R0603"))
    )
    (comp (ref "R42")
      (value "3.9Mohm")
      (footprint "eagle-import:R0603")
      (libsource (lib "eagle-import") (part "R-EU_R0603"))
    )
    (comp (ref "R43")
      (value "3.9Mohm")
      (footprint "eagle-import:R0603")
      (libsource (lib "eagle-import") (part "R-EU_R0603"))
    )
    (comp (ref "R44")
      (value "3.9Mohm")
      (footprint "eagle-import:R0603")
      (libsource (lib "eagle-import") (part "R-EU_R0603"))
    )
    (comp (ref "R45")
      (value "3.9Mohm")
      (footprint "eagle-import:R0603")
      (libsource (lib "eagle-import") (part "R-EU_R0603"))
    )
    (comp (ref "R46")
      (value "3.9Mohm")
      (footprint "eagle-import:R0603")
      (libsource (lib "eagle-import") (part "R-EU_R0603"))
    )
    (comp (ref "R47")
      (value "3.9Mohm")
      (footprint "eagle-import:R0603")
      (libsource (lib "eagle-import") (part "R-EU_R0603"))
    )
    (comp (ref "R48")
      (value "3.9Mohm")
      (footprint "eagle-import:R0603")
      (libsource (lib "eagle-import") (part "R-EU_R0603"))
    )
    (comp (ref "R49")
      (value "3.9Mohm")
      (footprint "eagle-import:R0603")
      (libsource (lib "eagle-import") (part "R-EU_R0603"))
    )
    (comp (ref "R50")
      (value "3.9Mohm")
      (footprint "eagle-import:R0603")
      (libsource (lib "eagle-import") (part "R-EU_R0603"))
    )
    (comp (ref "R51")
      (value "3.9Mohm")
      (footprint "eagle-import:R0603")
      (libsource (lib "eagle-import") (part "R-EU_R0603"))
    )
    (comp (ref "R52")
      (value "3.9Mohm")
      (footprint "eagle-import:R0603")
      (libsource (lib "eagle-import") (part "R-EU_R0603"))
    )
    (comp (ref "R53")
      (value "3.9Mohm")
      (footprint "eagle-import:R0603")
      (libsource (lib "eagle-import") (part "R-EU_R0603"))
    )
    (comp (ref "R54")
      (value "3.9Mohm")
      (footprint "eagle-import:R0603")
      (libsource (lib "eagle-import") (part "R-EU_R0603"))
    )
    (comp (ref "R55")
      (value "3.9Mohm")
      (footprint "eagle-import:R0603")
      (libsource (lib "eagle-import") (part "R-EU_R0603"))
    )
    (comp (ref "R56")
      (value "3.9Mohm")
      (footprint "eagle-import:R0603")
      (libsource (lib "eagle-import") (part "R-EU_R0603"))
    )
    (comp (ref "R57")
      (value "3.9Mohm")
      (footprint "eagle-import:R0603")
      (libsource (lib "eagle-import") (part "R-EU_R0603"))
    )
    (comp (ref "R58")
      (value "3.9Mohm")
      (footprint "eagle-import:R0603")
      (libsource (lib "eagle-import") (part "R-EU_R0603"))
    )
    (comp (ref "R59")
      (value "3.9Mohm")
      (footprint "eagle-import:R0603")
      (libsource (lib "eagle-import") (part "R-EU_R0603"))
    )
    (comp (ref "R60")
      (value "3.9Mohm")
      (footprint "eagle-import:R0603")
      (libsource (lib "eagle-import") (part "R-EU_R0603"))
    )
    (comp (ref "R61")
      (value "3.9Mohm")
      (footprint "eagle-import:R0603")
      (libsource (lib "eagle-import") (part "R-EU_R0603"))
    )
    (comp (ref "R62")
      (value "3.9Mohm")
      (footprint "eagle-import:R0603")
      (libsource (lib "eagle-import") (part "R-EU_R0603"))
    )
    (comp (ref "R63")
      (value "3.9Mohm")
      (footprint "eagle-import:R0603")
      (libsource (lib "eagle-import") (part "R-EU_R0603"))
    )
    (comp (ref "R64")
      (value "3.9Mohm")
      (footprint "eagle-import:R0603")
      (libsource (lib "eagle-import") (part "R-EU_R0603"))
    )
    (comp (ref "R65")
      (value "3.9Mohm")
      (footprint "eagle-import:R0603")
      (libsource (lib "eagle-import") (part "R-EU_R0603"))
    )
    (comp (ref "R66")
      (value "3.9Mohm")
      (footprint "eagle-import:R0603")
      (libsource (lib "eagle-import") (part "R-EU_R0603"))
    )
    (comp (ref "R67")
      (value "3.9Mohm")
      (footprint "eagle-import:R0603")
      (libsource (lib "eagle-import") (part "R-EU_R0603"))
    )
    (comp (ref "R68")
      (value "3.9Mohm")
      (footprint "eagle-import:R0603")
      (libsource (lib "eagle-import") (part "R-EU_R0603"))
    )
    (comp (ref "R69")
      (value "3.9Mohm")
      (footprint "eagle-import:R0603")
      (libsource (lib "eagle-import") (part "R-EU_R0603"))
    )
    (comp (ref "R70")
      (value "3.9Mohm")
      (footprint "eagle-import:R0603")
      (libsource (lib "eagle-import") (part "R-EU_R0603"))
    )
    (comp (ref "R71")
      (value "3.9Mohm")
      (footprint "eagle-import:R0603")
      (libsource (lib "eagle-import") (part "R-EU_R0603"))
    )
    (comp (ref "R72")
      (value "3.9Mohm")
      (footprint "eagle-import:R0603")
      (libsource (lib "eagle-import") (part "R-EU_R0603"))
    )
    (comp (ref "R73")
      (value "3.9Mohm")
      (footprint "eagle-import:R0603")
      (libsource (lib "eagle-import") (part "R-EU_R0603"))
    )
    (comp (ref "R74")
      (value "3.9Mohm")
      (footprint "eagle-import:R0603")
      (libsource (lib "eagle-import") (part "R-EU_R0603"))
    )
    (comp (ref "R75")
      (value "3.9Mohm")
      (footprint "eagle-import:R0603")
      (libsource (lib "eagle-import") (part "R-EU_R0603"))
    )
    (comp (ref "R76")
      (value "3.9Mohm")
      (footprint "eagle-import:R0603")
      (libsource (lib "eagle-import") (part "R-EU_R0603"))
    )
    (comp (ref "R77")
      (value "3.9Mohm")
      (footprint "eagle-import:R0603")
      (libsource (lib "eagle-import") (part "R-EU_R0603"))
    )
    (comp (ref "R78")
      (value "3.9Mohm")
      (footprint "eagle-import:R0603")
      (libsource (lib "eagle-import") (part "R-EU_R0603"))
    )
    (comp (ref "R79")
      (value "3.9Mohm")
      (footprint "eagle-import:R0603")
      (libsource (lib "eagle-import") (part "R-EU_R0603"))
    )
    (comp (ref "R80")
      (value "3.9Mohm")
      (footprint "eagle-import:R0603")
      (libsource (lib "eagle-import") (part "R-EU_R0603"))
    )
    (comp (ref "R81")
      (value "3.9Mohm")
      (footprint "eagle-import:R0603")
      (libsource (lib "eagle-import") (part "R-EU_R0603"))
    )
    (comp (ref "R82")
      (value "3.9Mohm")
      (footprint "eagle-import:R0603")
      (libsource (lib "eagle-import") (part "R-EU_R0603"))
    )
    (comp (ref "R83")
      (value "3.9Mohm")
      (footprint "eagle-import:R0603")
      (libsource (lib "eagle-import") (part "R-EU_R0603"))
    )
    (comp (ref "R84")
      (value "3.9Mohm")
      (footprint "eagle-import:R0603")
      (libsource (lib "eagle-import") (part "R-EU_R0603"))
    )
    (comp (ref "R85")
      (value "3.9Mohm")
      (footprint "eagle-import:R0603")
      (libsource (lib "eagle-import") (part "R-EU_R0603"))
    )
    (comp (ref "R86")
      (value "3.9Mohm")
      (footprint "eagle-import:R0603")
      (libsource (lib "eagle-import") (part "R-EU_R0603"))
    )
    (comp (ref "R87")
      (value "3.9Mohm")
      (footprint "eagle-import:R0603")
      (libsource (lib "eagle-import") (part "R-EU_R0603"))
    )
    (comp (ref "R88")
      (value "3.9Mohm")
      (footprint "eagle-import:R0603")
      (libsource (lib "eagle-import") (part "R-EU_R0603"))
    )
    (comp (ref "R89")
      (value "3.9Mohm")
      (footprint "eagle-import:R0603")
      (libsource (lib "eagle-import") (part "R-EU_R0603"))
    )
    (comp (ref "R90")
      (value "3.9Mohm")
      (footprint "eagle-import:R0603")
      (libsource (lib "eagle-import") (part "R-EU_R0603"))
    )
    (comp (ref "R91")
      (value "3.9Mohm")
      (footprint "eagle-import:R0603")
      (libsource (lib "eagle-import") (part "R-EU_R0603"))
    )
    (comp (ref "R92")
      (value "3.9Mohm")
      (footprint "eagle-import:R0603")
      (libsource (lib "eagle-import") (part "R-EU_R0603"))
    )
    (comp (ref "R93")
      (value "3.9Mohm")
      (footprint "eagle-import:R0603")
      (libsource (lib "eagle-import") (part "R-EU_R0603"))
    )
    (comp (ref "R94")
      (value "3.9Mohm")
      (footprint "eagle-import:R0603")
      (libsource (lib "eagle-import") (part "R-EU_R0603"))
    )
    (comp (ref "R95")
      (value "3.9Mohm")
      (footprint "eagle-import:R0603")
      (libsource (lib "eagle-import") (part "R-EU_R0603"))
    )
    (comp (ref "R96")
      (value "3.9Mohm")
      (footprint "eagle-import:R0603")
      (libsource (lib "eagle-import") (part "R-EU_R0603"))
    )
    (comp (ref "R97")
      (value "3.9Mohm")
      (footprint "eagle-import:R0603")
      (libsource (lib "eagle-import") (part "R-EU_R0603"))
    )
    (comp (ref "U1")
      (value "74HC4067")
      (footprint "eagle-import:SSOP24")
      (libsource (lib "eagle-import") (part "MUX-1X16"))
    )
    (comp (ref "U2")
      (value "74HC4067")
      (footprint "eagle-import:SSOP24")
      (libsource (lib "eagle-import") (part "MUX-1X16"))
    )
    (comp (ref "U3")
      (value "74HC4067")
      (footprint "eagle-import:SSOP24")
      (libsource (lib "eagle-import") (part "MUX-1X16"))
    )
    (comp (ref "U4")
      (value "74HC4067")
      (footprint "eagle-import:SSOP24")
      (libsource (lib "eagle-import") (part "MUX-1X16"))
    )
    (comp (ref "U5")
      (value "74HC4067")
      (footprint "eagle-import:SSOP24")
      (libsource (lib "eagle-import") (part "MUX-1X16"))
    )
    (comp (ref "U6")
      (value "74HC4067")
      (footprint "eagle-import:SSOP24")
      (libsource (lib "eagle-import") (part "MUX-1X16"))
    )
  )
  (nets
    (net (code "1") (name "+5V") (class "Default")
      (node (ref "C1") (pin "1") (pinfunction "1_1") (pintype "passive"))
      (node (ref "C10") (pin "1") (pinfunction "1_1") (pintype "passive"))
      (node (ref "C11") (pin "1") (pinfunction "1_1") (pintype "passive"))
      (node (ref "C12") (pin "1") (pinfunction "1_1") (pintype "passive"))
      (node (ref "C13") (pin "1") (pinfunction "1_1") (pintype "passive"))
      (node (ref "C14") (pin "1") (pinfunction "1_1") (pintype "passive"))
      (node (ref "C15") (pin "1") (pinfunction "1_1") (pintype "passive"))
      (node (ref "C16") (pin "1") (pinfunction "1_1") (pintype "passive"))
      (node (ref "C17") (pin "1") (pinfunction "1_1") (pintype "passive"))
      (node (ref "C18") (pin "1") (pinfunction "1_1") (pintype "passive"))
      (node (ref "C19") (pin "1") (pinfunction "1_1") (pintype "passive"))
      (node (ref "C2") (pin "1") (pinfunction "1_1") (pintype "passive"))
      (node (ref "C20") (pin "1") (pinfunction "1_1") (pintype "passive"))
      (node (ref "C21") (pin "1") (pinfunction "1_1") (pintype "passive"))
      (node (ref "C22") (pin "1") (pinfunction "1_1") (pintype "passive"))
      (node (ref "C23") (pin "1") (pinfunction "1_1") (pintype "passive"))
      (node (ref "C25") (pin "1") (pinfunction "1_1") (pintype "passive"))
      (node (ref "C3") (pin "1") (pinfunction "1_1") (pintype "passive"))
      (node (ref "C4") (pin "1") (pinfunction "1_1") (pintype "passive"))
      (node (ref "C5") (pin "1") (pinfunction "1_1") (pintype "passive"))
      (node (ref "C6") (pin "1") (pinfunction "1_1") (pintype "passive"))
      (node (ref "C7") (pin "1") (pinfunction "1_1") (pintype "passive"))
      (node (ref "C8") (pin "1") (pinfunction "1_1") (pintype "passive"))
      (node (ref "C9") (pin "1") (pinfunction "1_1") (pintype "passive"))
      (node (ref "IC1") (pin "4") (pinfunction "V+_4") (pintype "power_in"))
      (node (ref "IC10") (pin "4") (pinfunction "V+_4") (pintype "power_in"))
      (node (ref "IC11") (pin "4") (pinfunction "V+_4") (pintype "power_in"))
      (node (ref "IC12") (pin "4") (pinfunction "V+_4") (pintype "power_in"))
      (node (ref "IC13") (pin "4") (pinfunction "V+_4") (pintype "power_in"))
      (node (ref "IC14") (pin "4") (pinfunction "V+_4") (pintype "power_in"))
      (node (ref "IC15") (pin "4") (pinfunction "V+_4") (pintype "power_in"))
      (node (ref "IC16") (pin "4") (pinfunction "V+_4") (pintype "power_in"))
      (node (ref "IC17") (pin "4") (pinfunction "V+_4") (pintype "power_in"))
      (node (ref "IC18") (pin "4") (pinfunction "V+_4") (pintype "power_in"))
      (node (ref "IC19") (pin "4") (pinfunction "V+_4") (pintype "power_in"))
      (node (ref "IC2") (pin "4") (pinfunction "V+_4") (pintype "power_in"))
      (node (ref "IC20") (pin "4") (pinfunction "V+_4") (pintype "power_in"))
      (node (ref "IC21") (pin "4") (pinfunction "V+_4") (pintype "power_in"))
      (node (ref "IC22") (pin "4") (pinfunction "V+_4") (pintype "power_in"))
      (node (ref "IC23") (pin "4") (pinfunction "V+_4") (pintype "power_in"))
      (node (ref "IC24") (pin "4") (pinfunction "V+_4") (pintype "power_in"))
      (node (ref "IC3") (pin "4") (pinfunction "V+_4") (pintype "power_in"))
      (node (ref "IC4") (pin "4") (pinfunction "V+_4") (pintype "power_in"))
      (node (ref "IC5") (pin "4") (pinfunction "V+_4") (pintype "power_in"))
      (node (ref "IC6") (pin "4") (pinfunction "V+_4") (pintype "power_in"))
      (node (ref "IC7") (pin "4") (pinfunction "V+_4") (pintype "power_in"))
      (node (ref "IC8") (pin "4") (pinfunction "V+_4") (pintype "power_in"))
      (node (ref "IC9") (pin "4") (pinfunction "V+_4") (pintype "power_in"))
      (node (ref "J2") (pin "5") (pinfunction "5_5") (pintype "passive"))
      (node (ref "U1") (pin "24") (pinfunction "VCC_24") (pintype "bidirectional"))
      (node (ref "U2") (pin "24") (pinfunction "VCC_24") (pintype "bidirectional"))
      (node (ref "U3") (pin "24") (pinfunction "VCC_24") (pintype "bidirectional"))
      (node (ref "U4") (pin "24") (pinfunction "VCC_24") (pintype "bidirectional"))
      (node (ref "U5") (pin "24") (pinfunction "VCC_24") (pintype "bidirectional"))
      (node (ref "U6") (pin "24") (pinfunction "VCC_24") (pintype "bidirectional"))
    )
    (net (code "2") (name "/AO1") (class "Default")
      (node (ref "IC10") (pin "1") (pinfunction "OUT_1") (pintype "output"))
      (node (ref "R11") (pin "2") (pinfunction "2_2") (pintype "passive"))
      (node (ref "U1") (pin "2") (pinfunction "CH7_2") (pintype "bidirectional"))
    )
    (net (code "3") (name "/AO2") (class "Default")
      (node (ref "IC10") (pin "7") (pinfunction "OUT_7") (pintype "output"))
      (node (ref "R22") (pin "2") (pinfunction "2_2") (pintype "passive"))
      (node (ref "U1") (pin "3") (pinfunction "CH6_3") (pintype "bidirectional"))
    )
    (net (code "4") (name "/AO3") (class "Default")
      (node (ref "IC11") (pin "1") (pinfunction "OUT_1") (pintype "output"))
      (node (ref "R12") (pin "2") (pinfunction "2_2") (pintype "passive"))
      (node (ref "U1") (pin "4") (pinfunction "CH5_4") (pintype "bidirectional"))
    )
    (net (code "5") (name "/AO4") (class "Default")
      (node (ref "IC11") (pin "7") (pinfunction "OUT_7") (pintype "output"))
      (node (ref "R23") (pin "2") (pinfunction "2_2") (pintype "passive"))
      (node (ref "U1") (pin "5") (pinfunction "CH4_5") (pintype "bidirectional"))
    )
    (net (code "6") (name "/AO5") (class "Default")
      (node (ref "IC8") (pin "1") (pinfunction "OUT_1") (pintype "output"))
      (node (ref "R9") (pin "2") (pinfunction "2_2") (pintype "passive"))
      (node (ref "U1") (pin "23") (pinfunction "CH8_23") (pintype "bidirectional"))
    )
    (net (code "7") (name "/AO6") (class "Default")
      (node (ref "IC8") (pin "7") (pinfunction "OUT_7") (pintype "output"))
      (node (ref "R20") (pin "2") (pinfunction "2_2") (pintype "passive"))
      (node (ref "U1") (pin "22") (pinfunction "CH9_22") (pintype "bidirectional"))
    )
    (net (code "8") (name "/AO7") (class "Default")
      (node (ref "IC7") (pin "1") (pinfunction "OUT_1") (pintype "output"))
      (node (ref "R8") (pin "2") (pinfunction "2_2") (pintype "passive"))
      (node (ref "U1") (pin "21") (pinfunction "CH10_21") (pintype "bidirectional"))
    )
    (net (code "9") (name "/AO8") (class "Default")
      (node (ref "IC7") (pin "7") (pinfunction "OUT_7") (pintype "output"))
      (node (ref "R19") (pin "2") (pinfunction "2_2") (pintype "passive"))
      (node (ref "U1") (pin "20") (pinfunction "CH11_20") (pintype "bidirectional"))
    )
    (net (code "10") (name "/AO9") (class "Default")
      (node (ref "IC10") (pin "14") (pinfunction "OUT_14") (pintype "output"))
      (node (ref "R38") (pin "2") (pinfunction "2_2") (pintype "passive"))
      (node (ref "U1") (pin "6") (pinfunction "CH3_6") (pintype "bidirectional"))
    )
    (net (code "11") (name "/AO10") (class "Default")
      (node (ref "IC10") (pin "8") (pinfunction "OUT_8") (pintype "output"))
      (node (ref "R30") (pin "2") (pinfunction "2_2") (pintype "passive"))
      (node (ref "U1") (pin "7") (pinfunction "CH2_7") (pintype "bidirectional"))
    )
    (net (code "12") (name "/AO11") (class "Default")
      (node (ref "IC11") (pin "14") (pinfunction "OUT_14") (pintype "output"))
      (node (ref "R39") (pin "2") (pinfunction "2_2") (pintype "passive"))
      (node (ref "U1") (pin "8") (pinfunction "CH1_8") (pintype "bidirectional"))
    )
    (net (code "13") (name "/AO12") (class "Default")
      (node (ref "IC11") (pin "8") (pinfunction "OUT_8") (pintype "output"))
      (node (ref "R31") (pin "2") (pinfunction "2_2") (pintype "passive"))
      (node (ref "U1") (pin "9") (pinfunction "CH0_9") (pintype "bidirectional"))
    )
    (net (code "14") (name "/AO13") (class "Default")
      (node (ref "IC8") (pin "14") (pinfunction "OUT_14") (pintype "output"))
      (node (ref "R36") (pin "2") (pinfunction "2_2") (pintype "passive"))
      (node (ref "U1") (pin "19") (pinfunction "CH12_19") (pintype "bidirectional"))
    )
    (net (code "15") (name "/AO14") (class "Default")
      (node (ref "IC8") (pin "8") (pinfunction "OUT_8") (pintype "output"))
      (node (ref "R27") (pin "2") (pinfunction "2_2") (pintype "passive"))
      (node (ref "U1") (pin "18") (pinfunction "CH13_18") (pintype "bidirectional"))
    )
    (net (code "16") (name "/AO15") (class "Default")
      (node (ref "IC7") (pin "14") (pinfunction "OUT_14") (pintype "output"))
      (node (ref "R35") (pin "2") (pinfunction "2_2") (pintype "passive"))
      (node (ref "U1") (pin "17") (pinfunction "CH14_17") (pintype "bidirectional"))
    )
    (net (code "17") (name "/AO16") (class "Default")
      (node (ref "IC7") (pin "8") (pinfunction "OUT_8") (pintype "output"))
      (node (ref "R26") (pin "2") (pinfunction "2_2") (pintype "passive"))
      (node (ref "U1") (pin "16") (pinfunction "CH15_16") (pintype "bidirectional"))
    )
    (net (code "18") (name "/AR0") (class "Default")
      (node (ref "J1") (pin "1") (pinfunction "1_1") (pintype "passive"))
      (node (ref "U1") (pin "1") (pinfunction "COM_1") (pintype "bidirectional"))
    )
    (net (code "19") (name "/AR1") (class "Default")
      (node (ref "J1") (pin "2") (pinfunction "2_2") (pintype "passive"))
      (node (ref "U3") (pin "1") (pinfunction "COM_1") (pintype "bidirectional"))
    )
    (net (code "20") (name "/AR2") (class "Default")
      (node (ref "J1") (pin "3") (pinfunction "3_3") (pintype "passive"))
      (node (ref "U5") (pin "1") (pinfunction "COM_1") (pintype "bidirectional"))
    )
    (net (code "21") (name "/AR3") (class "Default")
      (node (ref "J1") (pin "4") (pinfunction "4_4") (pintype "passive"))
      (node (ref "U2") (pin "1") (pinfunction "COM_1") (pintype "bidirectional"))
    )
    (net (code "22") (name "/AR4") (class "Default")
      (node (ref "J1") (pin "5") (pinfunction "5_5") (pintype "passive"))
      (node (ref "U4") (pin "1") (pinfunction "COM_1") (pintype "bidirectional"))
    )
    (net (code "23") (name "/AR5") (class "Default")
      (node (ref "J1") (pin "6") (pinfunction "6_6") (pintype "passive"))
      (node (ref "U6") (pin "1") (pinfunction "COM_1") (pintype "bidirectional"))
    )
    (net (code "24") (name "/BO1") (class "Default")
      (node (ref "IC17") (pin "1") (pinfunction "OUT_1") (pintype "output"))
      (node (ref "R66") (pin "2") (pinfunction "2_2") (pintype "passive"))
      (node (ref "U3") (pin "2") (pinfunction "CH7_2") (pintype "bidirectional"))
    )
    (net (code "25") (name "/BO2") (class "Default")
      (node (ref "IC17") (pin "7") (pinfunction "OUT_7") (pintype "output"))
      (node (ref "R77") (pin "2") (pinfunction "2_2") (pintype "passive"))
      (node (ref "U3") (pin "3") (pinfunction "CH6_3") (pintype "bidirectional"))
    )
    (net (code "26") (name "/BO3") (class "Default")
      (node (ref "IC20") (pin "1") (pinfunction "OUT_1") (pintype "output"))
      (node (ref "R70") (pin "2") (pinfunction "2_2") (pintype "passive"))
      (node (ref "U3") (pin "4") (pinfunction "CH5_4") (pintype "bidirectional"))
    )
    (net (code "27") (name "/BO4") (class "Default")
      (node (ref "IC20") (pin "7") (pinfunction "OUT_7") (pintype "output"))
      (node (ref "R80") (pin "2") (pinfunction "2_2") (pintype "passive"))
      (node (ref "U3") (pin "5") (pinfunction "CH4_5") (pintype "bidirectional"))
    )
    (net (code "28") (name "/BO5") (class "Default")
      (node (ref "IC2") (pin "1") (pinfunction "OUT_1") (pintype "output"))
      (node (ref "R5") (pin "2") (pinfunction "2_2") (pintype "passive"))
      (node (ref "U3") (pin "23") (pinfunction "CH8_23") (pintype "bidirectional"))
    )
    (net (code "29") (name "/BO6") (class "Default")
      (node (ref "IC2") (pin "7") (pinfunction "OUT_7") (pintype "output"))
      (node (ref "R18") (pin "2") (pinfunction "2_2") (pintype "passive"))
      (node (ref "U3") (pin "22") (pinfunction "CH9_22") (pintype "bidirectional"))
    )
    (net (code "30") (name "/BO7") (class "Default")
      (node (ref "IC1") (pin "1") (pinfunction "OUT_1") (pintype "output"))
      (node (ref "R4") (pin "2") (pinfunction "2_2") (pintype "passive"))
      (node (ref "U3") (pin "21") (pinfunction "CH10_21") (pintype "bidirectional"))
    )
    (net (code "31") (name "/BO8") (class "Default")
      (node (ref "IC1") (pin "7") (pinfunction "OUT_7") (pintype "output"))
      (node (ref "R15") (pin "2") (pinfunction "2_2") (pintype "passive"))
      (node (ref "U3") (pin "20") (pinfunction "CH11_20") (pintype "bidirectional"))
    )
    (net (code "32") (name "/BO9") (class "Default")
      (node (ref "IC17") (pin "14") (pinfunction "OUT_14") (pintype "output"))
      (node (ref "R90") (pin "2") (pinfunction "2_2") (pintype "passive"))
      (node (ref "U3") (pin "6") (pinfunction "CH3_6") (pintype "bidirectional"))
    )
    (net (code "33") (name "/BO10") (class "Default")
      (node (ref "IC17") (pin "8") (pinfunction "OUT_8") (pintype "output"))
      (node (ref "R83") (pin "2") (pinfunction "2_2") (pintype "passive"))
      (node (ref "U3") (pin "7") (pinfunction "CH2_7") (pintype "bidirectional"))
    )
    (net (code "34") (name "/BO11") (class "Default")
      (node (ref "IC20") (pin "14") (pinfunction "OUT_14") (pintype "output"))
      (node (ref "R96") (pin "2") (pinfunction "2_2") (pintype "passive"))
      (node (ref "U3") (pin "8") (pinfunction "CH1_8") (pintype "bidirectional"))
    )
    (net (code "35") (name "/BO12") (class "Default")
      (node (ref "IC20") (pin "8") (pinfunction "OUT_8") (pintype "output"))
      (node (ref "R87") (pin "2") (pinfunction "2_2") (pintype "passive"))
      (node (ref "U3") (pin "9") (pinfunction "CH0_9") (pintype "bidirectional"))
    )
    (net (code "36") (name "/BO13") (class "Default")
      (node (ref "IC2") (pin "14") (pinfunction "OUT_14") (pintype "output"))
      (node (ref "R41") (pin "2") (pinfunction "2_2") (pintype "passive"))
      (node (ref "U3") (pin "19") (pinfunction "CH12_19") (pintype "bidirectional"))
    )
    (net (code "37") (name "/BO14") (class "Default")
      (node (ref "IC2") (pin "8") (pinfunction "OUT_8") (pintype "output"))
      (node (ref "R24") (pin "2") (pinfunction "2_2") (pintype "passive"))
      (node (ref "U3") (pin "18") (pinfunction "CH13_18") (pintype "bidirectional"))
    )
    (net (code "38") (name "/BO15") (class "Default")
      (node (ref "IC1") (pin "14") (pinfunction "OUT_14") (pintype "output"))
      (node (ref "R44") (pin "2") (pinfunction "2_2") (pintype "passive"))
      (node (ref "U3") (pin "17") (pinfunction "CH14_17") (pintype "bidirectional"))
    )
    (net (code "39") (name "/BO16") (class "Default")
      (node (ref "IC1") (pin "8") (pinfunction "OUT_8") (pintype "output"))
      (node (ref "R25") (pin "2") (pinfunction "2_2") (pintype "passive"))
      (node (ref "U3") (pin "16") (pinfunction "CH15_16") (pintype "bidirectional"))
    )
    (net (code "40") (name "/CO1") (class "Default")
      (node (ref "IC13") (pin "1") (pinfunction "OUT_1") (pintype "output"))
      (node (ref "R49") (pin "2") (pinfunction "2_2") (pintype "passive"))
      (node (ref "U5") (pin "2") (pinfunction "CH7_2") (pintype "bidirectional"))
    )
    (net (code "41") (name "/CO2") (class "Default")
      (node (ref "IC13") (pin "7") (pinfunction "OUT_7") (pintype "output"))
      (node (ref "R55") (pin "2") (pinfunction "2_2") (pintype "passive"))
      (node (ref "U5") (pin "3") (pinfunction "CH6_3") (pintype "bidirectional"))
    )
    (net (code "42") (name "/CO3") (class "Default")
      (node (ref "IC12") (pin "1") (pinfunction "OUT_1") (pintype "output"))
      (node (ref "R48") (pin "2") (pinfunction "2_2") (pintype "passive"))
      (node (ref "U5") (pin "4") (pinfunction "CH5_4") (pintype "bidirectional"))
    )
    (net (code "43") (name "/CO4") (class "Default")
      (node (ref "IC12") (pin "7") (pinfunction "OUT_7") (pintype "output"))
      (node (ref "R54") (pin "2") (pinfunction "2_2") (pintype "passive"))
      (node (ref "U5") (pin "5") (pinfunction "CH4_5") (pintype "bidirectional"))
    )
    (net (code "44") (name "/CO5") (class "Default")
      (node (ref "IC23") (pin "1") (pinfunction "OUT_1") (pintype "output"))
      (node (ref "R72") (pin "2") (pinfunction "2_2") (pintype "passive"))
      (node (ref "U5") (pin "23") (pinfunction "CH8_23") (pintype "bidirectional"))
    )
    (net (code "45") (name "/CO6") (class "Default")
      (node (ref "IC23") (pin "7") (pinfunction "OUT_7") (pintype "output"))
      (node (ref "R76") (pin "2") (pinfunction "2_2") (pintype "passive"))
      (node (ref "U5") (pin "22") (pinfunction "CH9_22") (pintype "bidirectional"))
    )
    (net (code "46") (name "/CO7") (class "Default")
      (node (ref "IC19") (pin "1") (pinfunction "OUT_1") (pintype "output"))
      (node (ref "R71") (pin "2") (pinfunction "2_2") (pintype "passive"))
      (node (ref "U5") (pin "21") (pinfunction "CH10_21") (pintype "bidirectional"))
    )
    (net (code "47") (name "/CO8") (class "Default")
      (node (ref "IC19") (pin "7") (pinfunction "OUT_7") (pintype "output"))
      (node (ref "R75") (pin "2") (pinfunction "2_2") (pintype "passive"))
      (node (ref "U5") (pin "20") (pinfunction "CH11_20") (pintype "bidirectional"))
    )
    (net (code "48") (name "/CO9") (class "Default")
      (node (ref "IC13") (pin "14") (pinfunction "OUT_14") (pintype "output"))
      (node (ref "R65") (pin "2") (pinfunction "2_2") (pintype "passive"))
      (node (ref "U5") (pin "6") (pinfunction "CH3_6") (pintype "bidirectional"))
    )
    (net (code "49") (name "/CO10") (class "Default")
      (node (ref "IC13") (pin "8") (pinfunction "OUT_8") (pintype "output"))
      (node (ref "R60") (pin "2") (pinfunction "2_2") (pintype "passive"))
      (node (ref "U5") (pin "7") (pinfunction "CH2_7") (pintype "bidirectional"))
    )
    (net (code "50") (name "/CO11") (class "Default")
      (node (ref "IC12") (pin "14") (pinfunction "OUT_14") (pintype "output"))
      (node (ref "R64") (pin "2") (pinfunction "2_2") (pintype "passive"))
      (node (ref "U5") (pin "8") (pinfunction "CH1_8") (pintype "bidirectional"))
    )
    (net (code "51") (name "/CO12") (class "Default")
      (node (ref "IC12") (pin "8") (pinfunction "OUT_8") (pintype "output"))
      (node (ref "R59") (pin "2") (pinfunction "2_2") (pintype "passive"))
      (node (ref "U5") (pin "9") (pinfunction "CH0_9") (pintype "bidirectional"))
    )
    (net (code "52") (name "/CO13") (class "Default")
      (node (ref "IC23") (pin "14") (pinfunction "OUT_14") (pintype "output"))
      (node (ref "R94") (pin "2") (pinfunction "2_2") (pintype "passive"))
      (node (ref "U5") (pin "19") (pinfunction "CH12_19") (pintype "bidirectional"))
    )
    (net (code "53") (name "/CO14") (class "Default")
      (node (ref "IC23") (pin "8") (pinfunction "OUT_8") (pintype "output"))
      (node (ref "R82") (pin "2") (pinfunction "2_2") (pintype "passive"))
      (node (ref "U5") (pin "18") (pinfunction "CH13_18") (pintype "bidirectional"))
    )
    (net (code "54") (name "/CO15") (class "Default")
      (node (ref "IC19") (pin "14") (pinfunction "OUT_14") (pintype "output"))
      (node (ref "R92") (pin "2") (pinfunction "2_2") (pintype "passive"))
      (node (ref "U5") (pin "17") (pinfunction "CH14_17") (pintype "bidirectional"))
    )
    (net (code "55") (name "/CO16") (class "Default")
      (node (ref "IC19") (pin "8") (pinfunction "OUT_8") (pintype "output"))
      (node (ref "R86") (pin "2") (pinfunction "2_2") (pintype "passive"))
      (node (ref "U5") (pin "16") (pinfunction "CH15_16") (pintype "bidirectional"))
    )
    (net (code "56") (name "/DO1") (class "Default")
      (node (ref "IC6") (pin "1") (pinfunction "OUT_1") (pintype "output"))
      (node (ref "R1") (pin "2") (pinfunction "2_2") (pintype "passive"))
      (node (ref "U2") (pin "2") (pinfunction "CH7_2") (pintype "bidirectional"))
    )
    (net (code "57") (name "/DO2") (class "Default")
      (node (ref "IC6") (pin "7") (pinfunction "OUT_7") (pintype "output"))
      (node (ref "R14") (pin "2") (pinfunction "2_2") (pintype "passive"))
      (node (ref "U2") (pin "3") (pinfunction "CH6_3") (pintype "bidirectional"))
    )
    (net (code "58") (name "/DO3") (class "Default")
      (node (ref "IC16") (pin "1") (pinfunction "OUT_1") (pintype "output"))
      (node (ref "R47") (pin "2") (pinfunction "2_2") (pintype "passive"))
      (node (ref "U2") (pin "4") (pinfunction "CH5_4") (pintype "bidirectional"))
    )
    (net (code "59") (name "/DO4") (class "Default")
      (node (ref "IC16") (pin "7") (pinfunction "OUT_7") (pintype "output"))
      (node (ref "R51") (pin "2") (pinfunction "2_2") (pintype "passive"))
      (node (ref "U2") (pin "5") (pinfunction "CH4_5") (pintype "bidirectional"))
    )
    (net (code "60") (name "/DO5") (class "Default")
      (node (ref "IC18") (pin "1") (pinfunction "OUT_1") (pintype "output"))
      (node (ref "R69") (pin "2") (pinfunction "2_2") (pintype "passive"))
      (node (ref "U2") (pin "23") (pinfunction "CH8_23") (pintype "bidirectional"))
    )
    (net (code "61") (name "/DO6") (class "Default")
      (node (ref "IC18") (pin "7") (pinfunction "OUT_7") (pintype "output"))
      (node (ref "R74") (pin "2") (pinfunction "2_2") (pintype "passive"))
      (node (ref "U2") (pin "22") (pinfunction "CH9_22") (pintype "bidirectional"))
    )
    (net (code "62") (name "/DO7") (class "Default")
      (node (ref "IC4") (pin "1") (pinfunction "OUT_1") (pintype "output"))
      (node (ref "R3") (pin "2") (pinfunction "2_2") (pintype "passive"))
      (node (ref "U2") (pin "21") (pinfunction "CH10_21") (pintype "bidirectional"))
    )
    (net (code "63") (name "/DO8") (class "Default")
      (node (ref "IC4") (pin "7") (pinfunction "OUT_7") (pintype "output"))
      (node (ref "R16") (pin "2") (pinfunction "2_2") (pintype "passive"))
      (node (ref "U2") (pin "20") (pinfunction "CH11_20") (pintype "bidirectional"))
    )
    (net (code "64") (name "/DO9") (class "Default")
      (node (ref "IC6") (pin "14") (pinfunction "OUT_14") (pintype "output"))
      (node (ref "R42") (pin "2") (pinfunction "2_2") (pintype "passive"))
      (node (ref "U2") (pin "6") (pinfunction "CH3_6") (pintype "bidirectional"))
    )
    (net (code "65") (name "/DO10") (class "Default")
      (node (ref "IC6") (pin "8") (pinfunction "OUT_8") (pintype "output"))
      (node (ref "R29") (pin "2") (pinfunction "2_2") (pintype "passive"))
      (node (ref "U2") (pin "7") (pinfunction "CH2_7") (pintype "bidirectional"))
    )
    (net (code "66") (name "/DO11") (class "Default")
      (node (ref "IC16") (pin "14") (pinfunction "OUT_14") (pintype "output"))
      (node (ref "R61") (pin "2") (pinfunction "2_2") (pintype "passive"))
      (node (ref "U2") (pin "8") (pinfunction "CH1_8") (pintype "bidirectional"))
    )
    (net (code "67") (name "/DO12") (class "Default")
      (node (ref "IC16") (pin "8") (pinfunction "OUT_8") (pintype "output"))
      (node (ref "R57") (pin "2") (pinfunction "2_2") (pintype "passive"))
      (node (ref "U2") (pin "9") (pinfunction "CH0_9") (pintype "bidirectional"))
    )
    (net (code "68") (name "/DO13") (class "Default")
      (node (ref "IC18") (pin "14") (pinfunction "OUT_14") (pintype "output"))
      (node (ref "R91") (pin "2") (pinfunction "2_2") (pintype "passive"))
      (node (ref "U2") (pin "19") (pinfunction "CH12_19") (pintype "bidirectional"))
    )
    (net (code "69") (name "/DO14") (class "Default")
      (node (ref "IC18") (pin "8") (pinfunction "OUT_8") (pintype "output"))
      (node (ref "R85") (pin "2") (pinfunction "2_2") (pintype "passive"))
      (node (ref "U2") (pin "18") (pinfunction "CH13_18") (pintype "bidirectional"))
    )
    (net (code "70") (name "/DO15") (class "Default")
      (node (ref "IC4") (pin "14") (pinfunction "OUT_14") (pintype "output"))
      (node (ref "R40") (pin "2") (pinfunction "2_2") (pintype "passive"))
      (node (ref "U2") (pin "17") (pinfunction "CH14_17") (pintype "bidirectional"))
    )
    (net (code "71") (name "/DO16") (class "Default")
      (node (ref "IC4") (pin "8") (pinfunction "OUT_8") (pintype "output"))
      (node (ref "R32") (pin "2") (pinfunction "2_2") (pintype "passive"))
      (node (ref "U2") (pin "16") (pinfunction "CH15_16") (pintype "bidirectional"))
    )
    (net (code "72") (name "/EO1") (class "Default")
      (node (ref "IC14") (pin "1") (pinfunction "OUT_1") (pintype "output"))
      (node (ref "R46") (pin "2") (pinfunction "2_2") (pintype "passive"))
      (node (ref "U4") (pin "2") (pinfunction "CH7_2") (pintype "bidirectional"))
    )
    (net (code "73") (name "/EO2") (class "Default")
      (node (ref "IC14") (pin "7") (pinfunction "OUT_7") (pintype "output"))
      (node (ref "R52") (pin "2") (pinfunction "2_2") (pintype "passive"))
      (node (ref "U4") (pin "3") (pinfunction "CH6_3") (pintype "bidirectional"))
    )
    (net (code "74") (name "/EO3") (class "Default")
      (node (ref "IC24") (pin "1") (pinfunction "OUT_1") (pintype "output"))
      (node (ref "R67") (pin "2") (pinfunction "2_2") (pintype "passive"))
      (node (ref "U4") (pin "4") (pinfunction "CH5_4") (pintype "bidirectional"))
    )
    (net (code "75") (name "/EO4") (class "Default")
      (node (ref "IC24") (pin "7") (pinfunction "OUT_7") (pintype "output"))
      (node (ref "R78") (pin "2") (pinfunction "2_2") (pintype "passive"))
      (node (ref "U4") (pin "5") (pinfunction "CH4_5") (pintype "bidirectional"))
    )
    (net (code "76") (name "/EO5") (class "Default")
      (node (ref "IC5") (pin "1") (pinfunction "OUT_1") (pintype "output"))
      (node (ref "R7") (pin "2") (pinfunction "2_2") (pintype "passive"))
      (node (ref "U4") (pin "23") (pinfunction "CH8_23") (pintype "bidirectional"))
    )
    (net (code "77") (name "/EO6") (class "Default")
      (node (ref "IC5") (pin "7") (pinfunction "OUT_7") (pintype "output"))
      (node (ref "R13") (pin "2") (pinfunction "2_2") (pintype "passive"))
      (node (ref "U4") (pin "22") (pinfunction "CH9_22") (pintype "bidirectional"))
    )
    (net (code "78") (name "/EO7") (class "Default")
      (node (ref "IC15") (pin "1") (pinfunction "OUT_1") (pintype "output"))
      (node (ref "R50") (pin "2") (pinfunction "2_2") (pintype "passive"))
      (node (ref "U4") (pin "21") (pinfunction "CH10_21") (pintype "bidirectional"))
    )
    (net (code "79") (name "/EO8") (class "Default")
      (node (ref "IC15") (pin "7") (pinfunction "OUT_7") (pintype "output"))
      (node (ref "R53") (pin "2") (pinfunction "2_2") (pintype "passive"))
      (node (ref "U4") (pin "20") (pinfunction "CH11_20") (pintype "bidirectional"))
    )
    (net (code "80") (name "/EO9") (class "Default")
      (node (ref "IC14") (pin "14") (pinfunction "OUT_14") (pintype "output"))
      (node (ref "R62") (pin "2") (pinfunction "2_2") (pintype "passive"))
      (node (ref "U4") (pin "6") (pinfunction "CH3_6") (pintype "bidirectional"))
    )
    (net (code "81") (name "/EO10") (class "Default")
      (node (ref "IC14") (pin "8") (pinfunction "OUT_8") (pintype "output"))
      (node (ref "R58") (pin "2") (pinfunction "2_2") (pintype "passive"))
      (node (ref "U4") (pin "7") (pinfunction "CH2_7") (pintype "bidirectional"))
    )
    (net (code "82") (name "/EO11") (class "Default")
      (node (ref "IC24") (pin "14") (pinfunction "OUT_14") (pintype "output"))
      (node (ref "R95") (pin "2") (pinfunction "2_2") (pintype "passive"))
      (node (ref "U4") (pin "8") (pinfunction "CH1_8") (pintype "bidirectional"))
    )
    (net (code "83") (name "/EO12") (class "Default")
      (node (ref "IC24") (pin "8") (pinfunction "OUT_8") (pintype "output"))
      (node (ref "R84") (pin "2") (pinfunction "2_2") (pintype "passive"))
      (node (ref "U4") (pin "9") (pinfunction "CH0_9") (pintype "bidirectional"))
    )
    (net (code "84") (name "/EO13") (class "Default")
      (node (ref "IC5") (pin "14") (pinfunction "OUT_14") (pintype "output"))
      (node (ref "R43") (pin "2") (pinfunction "2_2") (pintype "passive"))
      (node (ref "U4") (pin "19") (pinfunction "CH12_19") (pintype "bidirectional"))
    )
    (net (code "85") (name "/EO14") (class "Default")
      (node (ref "IC5") (pin "8") (pinfunction "OUT_8") (pintype "output"))
      (node (ref "R33") (pin "2") (pinfunction "2_2") (pintype "passive"))
      (node (ref "U4") (pin "18") (pinfunction "CH13_18") (pintype "bidirectional"))
    )
    (net (code "86") (name "/EO15") (class "Default")
      (node (ref "IC15") (pin "14") (pinfunction "OUT_14") (pintype "output"))
      (node (ref "R63") (pin "2") (pinfunction "2_2") (pintype "passive"))
      (node (ref "U4") (pin "17") (pinfunction "CH14_17") (pintype "bidirectional"))
    )
    (net (code "87") (name "/EO16") (class "Default")
      (node (ref "IC15") (pin "8") (pinfunction "OUT_8") (pintype "output"))
      (node (ref "R56") (pin "2") (pinfunction "2_2") (pintype "passive"))
      (node (ref "U4") (pin "16") (pinfunction "CH15_16") (pintype "bidirectional"))
    )
    (net (code "88") (name "/FO1") (class "Default")
      (node (ref "IC22") (pin "1") (pinfunction "OUT_1") (pintype "output"))
      (node (ref "R68") (pin "2") (pinfunction "2_2") (pintype "passive"))
      (node (ref "U6") (pin "2") (pinfunction "CH7_2") (pintype "bidirectional"))
    )
    (net (code "89") (name "/FO2") (class "Default")
      (node (ref "IC22") (pin "7") (pinfunction "OUT_7") (pintype "output"))
      (node (ref "R79") (pin "2") (pinfunction "2_2") (pintype "passive"))
      (node (ref "U6") (pin "3") (pinfunction "CH6_3") (pintype "bidirectional"))
    )
    (net (code "90") (name "/FO3") (class "Default")
      (node (ref "IC3") (pin "1") (pinfunction "OUT_1") (pintype "output"))
      (node (ref "R2") (pin "2") (pinfunction "2_2") (pintype "passive"))
      (node (ref "U6") (pin "4") (pinfunction "CH5_4") (pintype "bidirectional"))
    )
    (net (code "91") (name "/FO4") (class "Default")
      (node (ref "IC3") (pin "7") (pinfunction "OUT_7") (pintype "output"))
      (node (ref "R17") (pin "2") (pinfunction "2_2") (pintype "passive"))
      (node (ref "U6") (pin "5") (pinfunction "CH4_5") (pintype "bidirectional"))
    )
    (net (code "92") (name "/FO5") (class "Default")
      (node (ref "IC9") (pin "1") (pinfunction "OUT_1") (pintype "output"))
      (node (ref "R10") (pin "2") (pinfunction "2_2") (pintype "passive"))
      (node (ref "U6") (pin "23") (pinfunction "CH8_23") (pintype "bidirectional"))
    )
    (net (code "93") (name "/FO6") (class "Default")
      (node (ref "IC9") (pin "7") (pinfunction "OUT_7") (pintype "output"))
      (node (ref "R21") (pin "2") (pinfunction "2_2") (pintype "passive"))
      (node (ref "U6") (pin "22") (pinfunction "CH9_22") (pintype "bidirectional"))
    )
    (net (code "94") (name "/FO7") (class "Default")
      (node (ref "IC21") (pin "1") (pinfunction "OUT_1") (pintype "output"))
      (node (ref "R73") (pin "2") (pinfunction "2_2") (pintype "passive"))
      (node (ref "U6") (pin "21") (pinfunction "CH10_21") (pintype "bidirectional"))
    )
    (net (code "95") (name "/FO8") (class "Default")
      (node (ref "IC21") (pin "7") (pinfunction "OUT_7") (pintype "output"))
      (node (ref "R81") (pin "2") (pinfunction "2_2") (pintype "passive"))
      (node (ref "U6") (pin "20") (pinfunction "CH11_20") (pintype "bidirectional"))
    )
    (net (code "96") (name "/FO9") (class "Default")
      (node (ref "IC22") (pin "14") (pinfunction "OUT_14") (pintype "output"))
      (node (ref "R93") (pin "2") (pinfunction "2_2") (pintype "passive"))
      (node (ref "U6") (pin "6") (pinfunction "CH3_6") (pintype "bidirectional"))
    )
    (net (code "97") (name "/FO10") (class "Default")
      (node (ref "IC22") (pin "8") (pinfunction "OUT_8") (pintype "output"))
      (node (ref "R88") (pin "2") (pinfunction "2_2") (pintype "passive"))
      (node (ref "U6") (pin "7") (pinfunction "CH2_7") (pintype "bidirectional"))
    )
    (net (code "98") (name "/FO11") (class "Default")
      (node (ref "IC3") (pin "14") (pinfunction "OUT_14") (pintype "output"))
      (node (ref "R45") (pin "2") (pinfunction "2_2") (pintype "passive"))
      (node (ref "U6") (pin "8") (pinfunction "CH1_8") (pintype "bidirectional"))
    )
    (net (code "99") (name "/FO12") (class "Default")
      (node (ref "IC3") (pin "8") (pinfunction "OUT_8") (pintype "output"))
      (node (ref "R34") (pin "2") (pinfunction "2_2") (pintype "passive"))
      (node (ref "U6") (pin "9") (pinfunction "CH0_9") (pintype "bidirectional"))
    )
    (net (code "100") (name "/FO13") (class "Default")
      (node (ref "IC9") (pin "14") (pinfunction "OUT_14") (pintype "output"))
      (node (ref "R37") (pin "2") (pinfunction "2_2") (pintype "passive"))
      (node (ref "U6") (pin "19") (pinfunction "CH12_19") (pintype "bidirectional"))
    )
    (net (code "101") (name "/FO14") (class "Default")
      (node (ref "IC9") (pin "8") (pinfunction "OUT_8") (pintype "output"))
      (node (ref "R28") (pin "2") (pinfunction "2_2") (pintype "passive"))
      (node (ref "U6") (pin "18") (pinfunction "CH13_18") (pintype "bidirectional"))
    )
    (net (code "102") (name "/FO15") (class "Default")
      (node (ref "IC21") (pin "14") (pinfunction "OUT_14") (pintype "output"))
      (node (ref "R97") (pin "2") (pinfunction "2_2") (pintype "passive"))
      (node (ref "U6") (pin "17") (pinfunction "CH14_17") (pintype "bidirectional"))
    )
    (net (code "103") (name "/FO16") (class "Default")
      (node (ref "IC21") (pin "8") (pinfunction "OUT_8") (pintype "output"))
      (node (ref "R89") (pin "2") (pinfunction "2_2") (pintype "passive"))
      (node (ref "U6") (pin "16") (pinfunction "CH15_16") (pintype "bidirectional"))
    )
    (net (code "104") (name "/PD1") (class "Default")
      (node (ref "IC10") (pin "2") (pinfunction "-IN_2") (pintype "input"))
      (node (ref "PHD1") (pin "3") (pinfunction "2_3") (pintype "bidirectional"))
      (node (ref "PHD1") (pin "4") (pinfunction "2_4") (pintype "bidirectional"))
      (node (ref "R11") (pin "1") (pinfunction "1_1") (pintype "passive"))
    )
    (net (code "105") (name "/PD2") (class "Default")
      (node (ref "IC10") (pin "6") (pinfunction "-IN_6") (pintype "input"))
      (node (ref "PHD2") (pin "3") (pinfunction "2_3") (pintype "bidirectional"))
      (node (ref "PHD2") (pin "4") (pinfunction "2_4") (pintype "bidirectional"))
      (node (ref "R22") (pin "1") (pinfunction "1_1") (pintype "passive"))
    )
    (net (code "106") (name "/PD3") (class "Default")
      (node (ref "IC11") (pin "2") (pinfunction "-IN_2") (pintype "input"))
      (node (ref "PHD3") (pin "3") (pinfunction "2_3") (pintype "bidirectional"))
      (node (ref "PHD3") (pin "4") (pinfunction "2_4") (pintype "bidirectional"))
      (node (ref "R12") (pin "1") (pinfunction "1_1") (pintype "passive"))
    )
    (net (code "107") (name "/PD4") (class "Default")
      (node (ref "IC11") (pin "6") (pinfunction "-IN_6") (pintype "input"))
      (node (ref "PHD4") (pin "3") (pinfunction "2_3") (pintype "bidirectional"))
      (node (ref "PHD4") (pin "4") (pinfunction "2_4") (pintype "bidirectional"))
      (node (ref "R23") (pin "1") (pinfunction "1_1") (pintype "passive"))
    )
    (net (code "108") (name "/PD5") (class "Default")
      (node (ref "IC8") (pin "2") (pinfunction "-IN_2") (pintype "input"))
      (node (ref "PHD5") (pin "3") (pinfunction "2_3") (pintype "bidirectional"))
      (node (ref "PHD5") (pin "4") (pinfunction "2_4") (pintype "bidirectional"))
      (node (ref "R9") (pin "1") (pinfunction "1_1") (pintype "passive"))
    )
    (net (code "109") (name "/PD6") (class "Default")
      (node (ref "IC8") (pin "6") (pinfunction "-IN_6") (pintype "input"))
      (node (ref "PHD6") (pin "3") (pinfunction "2_3") (pintype "bidirectional"))
      (node (ref "PHD6") (pin "4") (pinfunction "2_4") (pintype "bidirectional"))
      (node (ref "R20") (pin "1") (pinfunction "1_1") (pintype "passive"))
    )
    (net (code "110") (name "/PD7") (class "Default")
      (node (ref "IC7") (pin "2") (pinfunction "-IN_2") (pintype "input"))
      (node (ref "PHD7") (pin "3") (pinfunction "2_3") (pintype "bidirectional"))
      (node (ref "PHD7") (pin "4") (pinfunction "2_4") (pintype "bidirectional"))
      (node (ref "R8") (pin "1") (pinfunction "1_1") (pintype "passive"))
    )
    (net (code "111") (name "/PD8") (class "Default")
      (node (ref "IC7") (pin "6") (pinfunction "-IN_6") (pintype "input"))
      (node (ref "PHD8") (pin "3") (pinfunction "2_3") (pintype "bidirectional"))
      (node (ref "PHD8") (pin "4") (pinfunction "2_4") (pintype "bidirectional"))
      (node (ref "R19") (pin "1") (pinfunction "1_1") (pintype "passive"))
    )
    (net (code "112") (name "/PD9") (class "Default")
      (node (ref "IC10") (pin "13") (pinfunction "-IN_13") (pintype "input"))
      (node (ref "PHD9") (pin "3") (pinfunction "2_3") (pintype "bidirectional"))
      (node (ref "PHD9") (pin "4") (pinfunction "2_4") (pintype "bidirectional"))
      (node (ref "R38") (pin "1") (pinfunction "1_1") (pintype "passive"))
    )
    (net (code "113") (name "/PD10") (class "Default")
      (node (ref "IC10") (pin "9") (pinfunction "-IN_9") (pintype "input"))
      (node (ref "PHD10") (pin "3") (pinfunction "2_3") (pintype "bidirectional"))
      (node (ref "PHD10") (pin "4") (pinfunction "2_4") (pintype "bidirectional"))
      (node (ref "R30") (pin "1") (pinfunction "1_1") (pintype "passive"))
    )
    (net (code "114") (name "/PD11") (class "Default")
      (node (ref "IC11") (pin "13") (pinfunction "-IN_13") (pintype "input"))
      (node (ref "PHD11") (pin "3") (pinfunction "2_3") (pintype "bidirectional"))
      (node (ref "PHD11") (pin "4") (pinfunction "2_4") (pintype "bidirectional"))
      (node (ref "R39") (pin "1") (pinfunction "1_1") (pintype "passive"))
    )
    (net (code "115") (name "/PD12") (class "Default")
      (node (ref "IC11") (pin "9") (pinfunction "-IN_9") (pintype "input"))
      (node (ref "PHD12") (pin "3") (pinfunction "2_3") (pintype "bidirectional"))
      (node (ref "PHD12") (pin "4") (pinfunction "2_4") (pintype "bidirectional"))
      (node (ref "R31") (pin "1") (pinfunction "1_1") (pintype "passive"))
    )
    (net (code "116") (name "/PD13") (class "Default")
      (node (ref "IC8") (pin "13") (pinfunction "-IN_13") (pintype "input"))
      (node (ref "PHD13") (pin "3") (pinfunction "2_3") (pintype "bidirectional"))
      (node (ref "PHD13") (pin "4") (pinfunction "2_4") (pintype "bidirectional"))
      (node (ref "R36") (pin "1") (pinfunction "1_1") (pintype "passive"))
    )
    (net (code "117") (name "/PD14") (class "Default")
      (node (ref "IC8") (pin "9") (pinfunction "-IN_9") (pintype "input"))
      (node (ref "PHD14") (pin "3") (pinfunction "2_3") (pintype "bidirectional"))
      (node (ref "PHD14") (pin "4") (pinfunction "2_4") (pintype "bidirectional"))
      (node (ref "R27") (pin "1") (pinfunction "1_1") (pintype "passive"))
    )
    (net (code "118") (name "/PD15") (class "Default")
      (node (ref "IC7") (pin "13") (pinfunction "-IN_13") (pintype "input"))
      (node (ref "PHD15") (pin "3") (pinfunction "2_3") (pintype "bidirectional"))
      (node (ref "PHD15") (pin "4") (pinfunction "2_4") (pintype "bidirectional"))
      (node (ref "R35") (pin "1") (pinfunction "1_1") (pintype "passive"))
    )
    (net (code "119") (name "/PD16") (class "Default")
      (node (ref "IC7") (pin "9") (pinfunction "-IN_9") (pintype "input"))
      (node (ref "PHD16") (pin "3") (pinfunction "2_3") (pintype "bidirectional"))
      (node (ref "PHD16") (pin "4") (pinfunction "2_4") (pintype "bidirectional"))
      (node (ref "R26") (pin "1") (pinfunction "1_1") (pintype "passive"))
    )
    (net (code "120") (name "/PD17") (class "Default")
      (node (ref "IC17") (pin "2") (pinfunction "-IN_2") (pintype "input"))
      (node (ref "PHD17") (pin "3") (pinfunction "2_3") (pintype "bidirectional"))
      (node (ref "PHD17") (pin "4") (pinfunction "2_4") (pintype "bidirectional"))
      (node (ref "R66") (pin "1") (pinfunction "1_1") (pintype "passive"))
    )
    (net (code "121") (name "/PD18") (class "Default")
      (node (ref "IC17") (pin "6") (pinfunction "-IN_6") (pintype "input"))
      (node (ref "PHD18") (pin "3") (pinfunction "2_3") (pintype "bidirectional"))
      (node (ref "PHD18") (pin "4") (pinfunction "2_4") (pintype "bidirectional"))
      (node (ref "R77") (pin "1") (pinfunction "1_1") (pintype "passive"))
    )
    (net (code "122") (name "/PD19") (class "Default")
      (node (ref "IC20") (pin "2") (pinfunction "-IN_2") (pintype "input"))
      (node (ref "PHD19") (pin "3") (pinfunction "2_3") (pintype "bidirectional"))
      (node (ref "PHD19") (pin "4") (pinfunction "2_4") (pintype "bidirectional"))
      (node (ref "R70") (pin "1") (pinfunction "1_1") (pintype "passive"))
    )
    (net (code "123") (name "/PD20") (class "Default")
      (node (ref "IC20") (pin "6") (pinfunction "-IN_6") (pintype "input"))
      (node (ref "PHD20") (pin "3") (pinfunction "2_3") (pintype "bidirectional"))
      (node (ref "PHD20") (pin "4") (pinfunction "2_4") (pintype "bidirectional"))
      (node (ref "R80") (pin "1") (pinfunction "1_1") (pintype "passive"))
    )
    (net (code "124") (name "/PD21") (class "Default")
      (node (ref "IC2") (pin "2") (pinfunction "-IN_2") (pintype "input"))
      (node (ref "PHD21") (pin "3") (pinfunction "2_3") (pintype "bidirectional"))
      (node (ref "PHD21") (pin "4") (pinfunction "2_4") (pintype "bidirectional"))
      (node (ref "R5") (pin "1") (pinfunction "1_1") (pintype "passive"))
    )
    (net (code "125") (name "/PD22") (class "Default")
      (node (ref "IC2") (pin "6") (pinfunction "-IN_6") (pintype "input"))
      (node (ref "PHD22") (pin "3") (pinfunction "2_3") (pintype "bidirectional"))
      (node (ref "PHD22") (pin "4") (pinfunction "2_4") (pintype "bidirectional"))
      (node (ref "R18") (pin "1") (pinfunction "1_1") (pintype "passive"))
    )
    (net (code "126") (name "/PD23") (class "Default")
      (node (ref "IC1") (pin "2") (pinfunction "-IN_2") (pintype "input"))
      (node (ref "PHD23") (pin "3") (pinfunction "2_3") (pintype "bidirectional"))
      (node (ref "PHD23") (pin "4") (pinfunction "2_4") (pintype "bidirectional"))
      (node (ref "R4") (pin "1") (pinfunction "1_1") (pintype "passive"))
    )
    (net (code "127") (name "/PD24") (class "Default")
      (node (ref "IC1") (pin "6") (pinfunction "-IN_6") (pintype "input"))
      (node (ref "PHD24") (pin "3") (pinfunction "2_3") (pintype "bidirectional"))
      (node (ref "PHD24") (pin "4") (pinfunction "2_4") (pintype "bidirectional"))
      (node (ref "R15") (pin "1") (pinfunction "1_1") (pintype "passive"))
    )
    (net (code "128") (name "/PD25") (class "Default")
      (node (ref "IC17") (pin "13") (pinfunction "-IN_13") (pintype "input"))
      (node (ref "PHD25") (pin "3") (pinfunction "2_3") (pintype "bidirectional"))
      (node (ref "PHD25") (pin "4") (pinfunction "2_4") (pintype "bidirectional"))
      (node (ref "R90") (pin "1") (pinfunction "1_1") (pintype "passive"))
    )
    (net (code "129") (name "/PD26") (class "Default")
      (node (ref "IC17") (pin "9") (pinfunction "-IN_9") (pintype "input"))
      (node (ref "PHD26") (pin "3") (pinfunction "2_3") (pintype "bidirectional"))
      (node (ref "PHD26") (pin "4") (pinfunction "2_4") (pintype "bidirectional"))
      (node (ref "R83") (pin "1") (pinfunction "1_1") (pintype "passive"))
    )
    (net (code "130") (name "/PD27") (class "Default")
      (node (ref "IC20") (pin "13") (pinfunction "-IN_13") (pintype "input"))
      (node (ref "PHD27") (pin "3") (pinfunction "2_3") (pintype "bidirectional"))
      (node (ref "PHD27") (pin "4") (pinfunction "2_4") (pintype "bidirectional"))
      (node (ref "R96") (pin "1") (pinfunction "1_1") (pintype "passive"))
    )
    (net (code "131") (name "/PD28") (class "Default")
      (node (ref "IC20") (pin "9") (pinfunction "-IN_9") (pintype "input"))
      (node (ref "PHD28") (pin "3") (pinfunction "2_3") (pintype "bidirectional"))
      (node (ref "PHD28") (pin "4") (pinfunction "2_4") (pintype "bidirectional"))
      (node (ref "R87") (pin "1") (pinfunction "1_1") (pintype "passive"))
    )
    (net (code "132") (name "/PD29") (class "Default")
      (node (ref "IC2") (pin "13") (pinfunction "-IN_13") (pintype "input"))
      (node (ref "PHD29") (pin "3") (pinfunction "2_3") (pintype "bidirectional"))
      (node (ref "PHD29") (pin "4") (pinfunction "2_4") (pintype "bidirectional"))
      (node (ref "R41") (pin "1") (pinfunction "1_1") (pintype "passive"))
    )
    (net (code "133") (name "/PD30") (class "Default")
      (node (ref "IC2") (pin "9") (pinfunction "-IN_9") (pintype "input"))
      (node (ref "PHD30") (pin "3") (pinfunction "2_3") (pintype "bidirectional"))
      (node (ref "PHD30") (pin "4") (pinfunction "2_4") (pintype "bidirectional"))
      (node (ref "R24") (pin "1") (pinfunction "1_1") (pintype "passive"))
    )
    (net (code "134") (name "/PD31") (class "Default")
      (node (ref "IC1") (pin "13") (pinfunction "-IN_13") (pintype "input"))
      (node (ref "PHD31") (pin "3") (pinfunction "2_3") (pintype "bidirectional"))
      (node (ref "PHD31") (pin "4") (pinfunction "2_4") (pintype "bidirectional"))
      (node (ref "R44") (pin "1") (pinfunction "1_1") (pintype "passive"))
    )
    (net (code "135") (name "/PD32") (class "Default")
      (node (ref "IC1") (pin "9") (pinfunction "-IN_9") (pintype "input"))
      (node (ref "PHD32") (pin "3") (pinfunction "2_3") (pintype "bidirectional"))
      (node (ref "PHD32") (pin "4") (pinfunction "2_4") (pintype "bidirectional"))
      (node (ref "R25") (pin "1") (pinfunction "1_1") (pintype "passive"))
    )
    (net (code "136") (name "/PD33") (class "Default")
      (node (ref "IC13") (pin "2") (pinfunction "-IN_2") (pintype "input"))
      (node (ref "PHD33") (pin "3") (pinfunction "2_3") (pintype "bidirectional"))
      (node (ref "PHD33") (pin "4") (pinfunction "2_4") (pintype "bidirectional"))
      (node (ref "R49") (pin "1") (pinfunction "1_1") (pintype "passive"))
    )
    (net (code "137") (name "/PD34") (class "Default")
      (node (ref "IC13") (pin "6") (pinfunction "-IN_6") (pintype "input"))
      (node (ref "PHD34") (pin "3") (pinfunction "2_3") (pintype "bidirectional"))
      (node (ref "PHD34") (pin "4") (pinfunction "2_4") (pintype "bidirectional"))
      (node (ref "R55") (pin "1") (pinfunction "1_1") (pintype "passive"))
    )
    (net (code "138") (name "/PD35") (class "Default")
      (node (ref "IC12") (pin "2") (pinfunction "-IN_2") (pintype "input"))
      (node (ref "PHD35") (pin "3") (pinfunction "2_3") (pintype "bidirectional"))
      (node (ref "PHD35") (pin "4") (pinfunction "2_4") (pintype "bidirectional"))
      (node (ref "R48") (pin "1") (pinfunction "1_1") (pintype "passive"))
    )
    (net (code "139") (name "/PD36") (class "Default")
      (node (ref "IC12") (pin "6") (pinfunction "-IN_6") (pintype "input"))
      (node (ref "PHD36") (pin "3") (pinfunction "2_3") (pintype "bidirectional"))
      (node (ref "PHD36") (pin "4") (pinfunction "2_4") (pintype "bidirectional"))
      (node (ref "R54") (pin "1") (pinfunction "1_1") (pintype "passive"))
    )
    (net (code "140") (name "/PD37") (class "Default")
      (node (ref "IC23") (pin "2") (pinfunction "-IN_2") (pintype "input"))
      (node (ref "PHD37") (pin "3") (pinfunction "2_3") (pintype "bidirectional"))
      (node (ref "PHD37") (pin "4") (pinfunction "2_4") (pintype "bidirectional"))
      (node (ref "R72") (pin "1") (pinfunction "1_1") (pintype "passive"))
    )
    (net (code "141") (name "/PD38") (class "Default")
      (node (ref "IC23") (pin "6") (pinfunction "-IN_6") (pintype "input"))
      (node (ref "PHD38") (pin "3") (pinfunction "2_3") (pintype "bidirectional"))
      (node (ref "PHD38") (pin "4") (pinfunction "2_4") (pintype "bidirectional"))
      (node (ref "R76") (pin "1") (pinfunction "1_1") (pintype "passive"))
    )
    (net (code "142") (name "/PD39") (class "Default")
      (node (ref "IC19") (pin "2") (pinfunction "-IN_2") (pintype "input"))
      (node (ref "PHD39") (pin "3") (pinfunction "2_3") (pintype "bidirectional"))
      (node (ref "PHD39") (pin "4") (pinfunction "2_4") (pintype "bidirectional"))
      (node (ref "R71") (pin "1") (pinfunction "1_1") (pintype "passive"))
    )
    (net (code "143") (name "/PD40") (class "Default")
      (node (ref "IC19") (pin "6") (pinfunction "-IN_6") (pintype "input"))
      (node (ref "PHD40") (pin "3") (pinfunction "2_3") (pintype "bidirectional"))
      (node (ref "PHD40") (pin "4") (pinfunction "2_4") (pintype "bidirectional"))
      (node (ref "R75") (pin "1") (pinfunction "1_1") (pintype "passive"))
    )
    (net (code "144") (name "/PD41") (class "Default")
      (node (ref "IC13") (pin "13") (pinfunction "-IN_13") (pintype "input"))
      (node (ref "PHD41") (pin "3") (pinfunction "2_3") (pintype "bidirectional"))
      (node (ref "PHD41") (pin "4") (pinfunction "2_4") (pintype "bidirectional"))
      (node (ref "R65") (pin "1") (pinfunction "1_1") (pintype "passive"))
    )
    (net (code "145") (name "/PD42") (class "Default")
      (node (ref "IC13") (pin "9") (pinfunction "-IN_9") (pintype "input"))
      (node (ref "PHD42") (pin "3") (pinfunction "2_3") (pintype "bidirectional"))
      (node (ref "PHD42") (pin "4") (pinfunction "2_4") (pintype "bidirectional"))
      (node (ref "R60") (pin "1") (pinfunction "1_1") (pintype "passive"))
    )
    (net (code "146") (name "/PD43") (class "Default")
      (node (ref "IC12") (pin "13") (pinfunction "-IN_13") (pintype "input"))
      (node (ref "PHD43") (pin "3") (pinfunction "2_3") (pintype "bidirectional"))
      (node (ref "PHD43") (pin "4") (pinfunction "2_4") (pintype "bidirectional"))
      (node (ref "R64") (pin "1") (pinfunction "1_1") (pintype "passive"))
    )
    (net (code "147") (name "/PD44") (class "Default")
      (node (ref "IC12") (pin "9") (pinfunction "-IN_9") (pintype "input"))
      (node (ref "PHD44") (pin "3") (pinfunction "2_3") (pintype "bidirectional"))
      (node (ref "PHD44") (pin "4") (pinfunction "2_4") (pintype "bidirectional"))
      (node (ref "R59") (pin "1") (pinfunction "1_1") (pintype "passive"))
    )
    (net (code "148") (name "/PD45") (class "Default")
      (node (ref "IC23") (pin "13") (pinfunction "-IN_13") (pintype "input"))
      (node (ref "PHD45") (pin "3") (pinfunction "2_3") (pintype "bidirectional"))
      (node (ref "PHD45") (pin "4") (pinfunction "2_4") (pintype "bidirectional"))
      (node (ref "R94") (pin "1") (pinfunction "1_1") (pintype "passive"))
    )
    (net (code "149") (name "/PD46") (class "Default")
      (node (ref "IC23") (pin "9") (pinfunction "-IN_9") (pintype "input"))
      (node (ref "PHD46") (pin "3") (pinfunction "2_3") (pintype "bidirectional"))
      (node (ref "PHD46") (pin "4") (pinfunction "2_4") (pintype "bidirectional"))
      (node (ref "R82") (pin "1") (pinfunction "1_1") (pintype "passive"))
    )
    (net (code "150") (name "/PD47") (class "Default")
      (node (ref "IC19") (pin "13") (pinfunction "-IN_13") (pintype "input"))
      (node (ref "PHD47") (pin "3") (pinfunction "2_3") (pintype "bidirectional"))
      (node (ref "PHD47") (pin "4") (pinfunction "2_4") (pintype "bidirectional"))
      (node (ref "R92") (pin "1") (pinfunction "1_1") (pintype "passive"))
    )
    (net (code "151") (name "/PD48") (class "Default")
      (node (ref "IC19") (pin "9") (pinfunction "-IN_9") (pintype "input"))
      (node (ref "PHD48") (pin "3") (pinfunction "2_3") (pintype "bidirectional"))
      (node (ref "PHD48") (pin "4") (pinfunction "2_4") (pintype "bidirectional"))
      (node (ref "R86") (pin "1") (pinfunction "1_1") (pintype "passive"))
    )
    (net (code "152") (name "/PD49") (class "Default")
      (node (ref "IC6") (pin "2") (pinfunction "-IN_2") (pintype "input"))
      (node (ref "PHD49") (pin "3") (pinfunction "2_3") (pintype "bidirectional"))
      (node (ref "PHD49") (pin "4") (pinfunction "2_4") (pintype "bidirectional"))
      (node (ref "R1") (pin "1") (pinfunction "1_1") (pintype "passive"))
    )
    (net (code "153") (name "/PD50") (class "Default")
      (node (ref "IC6") (pin "6") (pinfunction "-IN_6") (pintype "input"))
      (node (ref "PHD50") (pin "3") (pinfunction "2_3") (pintype "bidirectional"))
      (node (ref "PHD50") (pin "4") (pinfunction "2_4") (pintype "bidirectional"))
      (node (ref "R14") (pin "1") (pinfunction "1_1") (pintype "passive"))
    )
    (net (code "154") (name "/PD51") (class "Default")
      (node (ref "IC16") (pin "2") (pinfunction "-IN_2") (pintype "input"))
      (node (ref "PHD51") (pin "3") (pinfunction "2_3") (pintype "bidirectional"))
      (node (ref "PHD51") (pin "4") (pinfunction "2_4") (pintype "bidirectional"))
      (node (ref "R47") (pin "1") (pinfunction "1_1") (pintype "passive"))
    )
    (net (code "155") (name "/PD52") (class "Default")
      (node (ref "IC16") (pin "6") (pinfunction "-IN_6") (pintype "input"))
      (node (ref "PHD52") (pin "3") (pinfunction "2_3") (pintype "bidirectional"))
      (node (ref "PHD52") (pin "4") (pinfunction "2_4") (pintype "bidirectional"))
      (node (ref "R51") (pin "1") (pinfunction "1_1") (pintype "passive"))
    )
    (net (code "156") (name "/PD53") (class "Default")
      (node (ref "IC18") (pin "2") (pinfunction "-IN_2") (pintype "input"))
      (node (ref "PHD53") (pin "3") (pinfunction "2_3") (pintype "bidirectional"))
      (node (ref "PHD53") (pin "4") (pinfunction "2_4") (pintype "bidirectional"))
      (node (ref "R69") (pin "1") (pinfunction "1_1") (pintype "passive"))
    )
    (net (code "157") (name "/PD54") (class "Default")
      (node (ref "IC18") (pin "6") (pinfunction "-IN_6") (pintype "input"))
      (node (ref "PHD54") (pin "3") (pinfunction "2_3") (pintype "bidirectional"))
      (node (ref "PHD54") (pin "4") (pinfunction "2_4") (pintype "bidirectional"))
      (node (ref "R74") (pin "1") (pinfunction "1_1") (pintype "passive"))
    )
    (net (code "158") (name "/PD55") (class "Default")
      (node (ref "IC4") (pin "2") (pinfunction "-IN_2") (pintype "input"))
      (node (ref "PHD55") (pin "3") (pinfunction "2_3") (pintype "bidirectional"))
      (node (ref "PHD55") (pin "4") (pinfunction "2_4") (pintype "bidirectional"))
      (node (ref "R3") (pin "1") (pinfunction "1_1") (pintype "passive"))
    )
    (net (code "159") (name "/PD56") (class "Default")
      (node (ref "IC4") (pin "6") (pinfunction "-IN_6") (pintype "input"))
      (node (ref "PHD56") (pin "3") (pinfunction "2_3") (pintype "bidirectional"))
      (node (ref "PHD56") (pin "4") (pinfunction "2_4") (pintype "bidirectional"))
      (node (ref "R16") (pin "1") (pinfunction "1_1") (pintype "passive"))
    )
    (net (code "160") (name "/PD57") (class "Default")
      (node (ref "IC6") (pin "13") (pinfunction "-IN_13") (pintype "input"))
      (node (ref "PHD57") (pin "3") (pinfunction "2_3") (pintype "bidirectional"))
      (node (ref "PHD57") (pin "4") (pinfunction "2_4") (pintype "bidirectional"))
      (node (ref "R42") (pin "1") (pinfunction "1_1") (pintype "passive"))
    )
    (net (code "161") (name "/PD58") (class "Default")
      (node (ref "IC6") (pin "9") (pinfunction "-IN_9") (pintype "input"))
      (node (ref "PHD58") (pin "3") (pinfunction "2_3") (pintype "bidirectional"))
      (node (ref "PHD58") (pin "4") (pinfunction "2_4") (pintype "bidirectional"))
      (node (ref "R29") (pin "1") (pinfunction "1_1") (pintype "passive"))
    )
    (net (code "162") (name "/PD59") (class "Default")
      (node (ref "IC16") (pin "13") (pinfunction "-IN_13") (pintype "input"))
      (node (ref "PHD59") (pin "3") (pinfunction "2_3") (pintype "bidirectional"))
      (node (ref "PHD59") (pin "4") (pinfunction "2_4") (pintype "bidirectional"))
      (node (ref "R61") (pin "1") (pinfunction "1_1") (pintype "passive"))
    )
    (net (code "163") (name "/PD60") (class "Default")
      (node (ref "IC16") (pin "9") (pinfunction "-IN_9") (pintype "input"))
      (node (ref "PHD60") (pin "3") (pinfunction "2_3") (pintype "bidirectional"))
      (node (ref "PHD60") (pin "4") (pinfunction "2_4") (pintype "bidirectional"))
      (node (ref "R57") (pin "1") (pinfunction "1_1") (pintype "passive"))
    )
    (net (code "164") (name "/PD61") (class "Default")
      (node (ref "IC18") (pin "13") (pinfunction "-IN_13") (pintype "input"))
      (node (ref "PHD61") (pin "3") (pinfunction "2_3") (pintype "bidirectional"))
      (node (ref "PHD61") (pin "4") (pinfunction "2_4") (pintype "bidirectional"))
      (node (ref "R91") (pin "1") (pinfunction "1_1") (pintype "passive"))
    )
    (net (code "165") (name "/PD62") (class "Default")
      (node (ref "IC18") (pin "9") (pinfunction "-IN_9") (pintype "input"))
      (node (ref "PHD62") (pin "3") (pinfunction "2_3") (pintype "bidirectional"))
      (node (ref "PHD62") (pin "4") (pinfunction "2_4") (pintype "bidirectional"))
      (node (ref "R85") (pin "1") (pinfunction "1_1") (pintype "passive"))
    )
    (net (code "166") (name "/PD63") (class "Default")
      (node (ref "IC4") (pin "13") (pinfunction "-IN_13") (pintype "input"))
      (node (ref "PHD63") (pin "3") (pinfunction "2_3") (pintype "bidirectional"))
      (node (ref "PHD63") (pin "4") (pinfunction "2_4") (pintype "bidirectional"))
      (node (ref "R40") (pin "1") (pinfunction "1_1") (pintype "passive"))
    )
    (net (code "167") (name "/PD64") (class "Default")
      (node (ref "IC4") (pin "9") (pinfunction "-IN_9") (pintype "input"))
      (node (ref "PHD64") (pin "3") (pinfunction "2_3") (pintype "bidirectional"))
      (node (ref "PHD64") (pin "4") (pinfunction "2_4") (pintype "bidirectional"))
      (node (ref "R32") (pin "1") (pinfunction "1_1") (pintype "passive"))
    )
    (net (code "168") (name "/PD65") (class "Default")
      (node (ref "IC14") (pin "2") (pinfunction "-IN_2") (pintype "input"))
      (node (ref "PHD65") (pin "3") (pinfunction "2_3") (pintype "bidirectional"))
      (node (ref "PHD65") (pin "4") (pinfunction "2_4") (pintype "bidirectional"))
      (node (ref "R46") (pin "1") (pinfunction "1_1") (pintype "passive"))
    )
    (net (code "169") (name "/PD66") (class "Default")
      (node (ref "IC14") (pin "6") (pinfunction "-IN_6") (pintype "input"))
      (node (ref "PHD66") (pin "3") (pinfunction "2_3") (pintype "bidirectional"))
      (node (ref "PHD66") (pin "4") (pinfunction "2_4") (pintype "bidirectional"))
      (node (ref "R52") (pin "1") (pinfunction "1_1") (pintype "passive"))
    )
    (net (code "170") (name "/PD67") (class "Default")
      (node (ref "IC24") (pin "2") (pinfunction "-IN_2") (pintype "input"))
      (node (ref "PHD67") (pin "3") (pinfunction "2_3") (pintype "bidirectional"))
      (node (ref "PHD67") (pin "4") (pinfunction "2_4") (pintype "bidirectional"))
      (node (ref "R67") (pin "1") (pinfunction "1_1") (pintype "passive"))
    )
    (net (code "171") (name "/PD68") (class "Default")
      (node (ref "IC24") (pin "6") (pinfunction "-IN_6") (pintype "input"))
      (node (ref "PHD68") (pin "3") (pinfunction "2_3") (pintype "bidirectional"))
      (node (ref "PHD68") (pin "4") (pinfunction "2_4") (pintype "bidirectional"))
      (node (ref "R78") (pin "1") (pinfunction "1_1") (pintype "passive"))
    )
    (net (code "172") (name "/PD69") (class "Default")
      (node (ref "IC5") (pin "2") (pinfunction "-IN_2") (pintype "input"))
      (node (ref "PHD69") (pin "3") (pinfunction "2_3") (pintype "bidirectional"))
      (node (ref "PHD69") (pin "4") (pinfunction "2_4") (pintype "bidirectional"))
      (node (ref "R7") (pin "1") (pinfunction "1_1") (pintype "passive"))
    )
    (net (code "173") (name "/PD70") (class "Default")
      (node (ref "IC5") (pin "6") (pinfunction "-IN_6") (pintype "input"))
      (node (ref "PHD70") (pin "3") (pinfunction "2_3") (pintype "bidirectional"))
      (node (ref "PHD70") (pin "4") (pinfunction "2_4") (pintype "bidirectional"))
      (node (ref "R13") (pin "1") (pinfunction "1_1") (pintype "passive"))
    )
    (net (code "174") (name "/PD71") (class "Default")
      (node (ref "IC15") (pin "2") (pinfunction "-IN_2") (pintype "input"))
      (node (ref "PHD71") (pin "3") (pinfunction "2_3") (pintype "bidirectional"))
      (node (ref "PHD71") (pin "4") (pinfunction "2_4") (pintype "bidirectional"))
      (node (ref "R50") (pin "1") (pinfunction "1_1") (pintype "passive"))
    )
    (net (code "175") (name "/PD72") (class "Default")
      (node (ref "IC15") (pin "6") (pinfunction "-IN_6") (pintype "input"))
      (node (ref "PHD72") (pin "3") (pinfunction "2_3") (pintype "bidirectional"))
      (node (ref "PHD72") (pin "4") (pinfunction "2_4") (pintype "bidirectional"))
      (node (ref "R53") (pin "1") (pinfunction "1_1") (pintype "passive"))
    )
    (net (code "176") (name "/PD73") (class "Default")
      (node (ref "IC14") (pin "13") (pinfunction "-IN_13") (pintype "input"))
      (node (ref "PHD73") (pin "3") (pinfunction "2_3") (pintype "bidirectional"))
      (node (ref "PHD73") (pin "4") (pinfunction "2_4") (pintype "bidirectional"))
      (node (ref "R62") (pin "1") (pinfunction "1_1") (pintype "passive"))
    )
    (net (code "177") (name "/PD74") (class "Default")
      (node (ref "IC14") (pin "9") (pinfunction "-IN_9") (pintype "input"))
      (node (ref "PHD74") (pin "3") (pinfunction "2_3") (pintype "bidirectional"))
      (node (ref "PHD74") (pin "4") (pinfunction "2_4") (pintype "bidirectional"))
      (node (ref "R58") (pin "1") (pinfunction "1_1") (pintype "passive"))
    )
    (net (code "178") (name "/PD75") (class "Default")
      (node (ref "IC24") (pin "13") (pinfunction "-IN_13") (pintype "input"))
      (node (ref "PHD75") (pin "3") (pinfunction "2_3") (pintype "bidirectional"))
      (node (ref "PHD75") (pin "4") (pinfunction "2_4") (pintype "bidirectional"))
      (node (ref "R95") (pin "1") (pinfunction "1_1") (pintype "passive"))
    )
    (net (code "179") (name "/PD76") (class "Default")
      (node (ref "IC24") (pin "9") (pinfunction "-IN_9") (pintype "input"))
      (node (ref "PHD76") (pin "3") (pinfunction "2_3") (pintype "bidirectional"))
      (node (ref "PHD76") (pin "4") (pinfunction "2_4") (pintype "bidirectional"))
      (node (ref "R84") (pin "1") (pinfunction "1_1") (pintype "passive"))
    )
    (net (code "180") (name "/PD77") (class "Default")
      (node (ref "IC5") (pin "13") (pinfunction "-IN_13") (pintype "input"))
      (node (ref "PHD77") (pin "3") (pinfunction "2_3") (pintype "bidirectional"))
      (node (ref "PHD77") (pin "4") (pinfunction "2_4") (pintype "bidirectional"))
      (node (ref "R43") (pin "1") (pinfunction "1_1") (pintype "passive"))
    )
    (net (code "181") (name "/PD78") (class "Default")
      (node (ref "IC5") (pin "9") (pinfunction "-IN_9") (pintype "input"))
      (node (ref "PHD78") (pin "3") (pinfunction "2_3") (pintype "bidirectional"))
      (node (ref "PHD78") (pin "4") (pinfunction "2_4") (pintype "bidirectional"))
      (node (ref "R33") (pin "1") (pinfunction "1_1") (pintype "passive"))
    )
    (net (code "182") (name "/PD79") (class "Default")
      (node (ref "IC15") (pin "13") (pinfunction "-IN_13") (pintype "input"))
      (node (ref "PHD79") (pin "3") (pinfunction "2_3") (pintype "bidirectional"))
      (node (ref "PHD79") (pin "4") (pinfunction "2_4") (pintype "bidirectional"))
      (node (ref "R63") (pin "1") (pinfunction "1_1") (pintype "passive"))
    )
    (net (code "183") (name "/PD80") (class "Default")
      (node (ref "IC15") (pin "9") (pinfunction "-IN_9") (pintype "input"))
      (node (ref "PHD80") (pin "3") (pinfunction "2_3") (pintype "bidirectional"))
      (node (ref "PHD80") (pin "4") (pinfunction "2_4") (pintype "bidirectional"))
      (node (ref "R56") (pin "1") (pinfunction "1_1") (pintype "passive"))
    )
    (net (code "184") (name "/PD81") (class "Default")
      (node (ref "IC22") (pin "2") (pinfunction "-IN_2") (pintype "input"))
      (node (ref "PHD81") (pin "3") (pinfunction "2_3") (pintype "bidirectional"))
      (node (ref "PHD81") (pin "4") (pinfunction "2_4") (pintype "bidirectional"))
      (node (ref "R68") (pin "1") (pinfunction "1_1") (pintype "passive"))
    )
    (net (code "185") (name "/PD82") (class "Default")
      (node (ref "IC22") (pin "6") (pinfunction "-IN_6") (pintype "input"))
      (node (ref "PHD82") (pin "3") (pinfunction "2_3") (pintype "bidirectional"))
      (node (ref "PHD82") (pin "4") (pinfunction "2_4") (pintype "bidirectional"))
      (node (ref "R79") (pin "1") (pinfunction "1_1") (pintype "passive"))
    )
    (net (code "186") (name "/PD83") (class "Default")
      (node (ref "IC3") (pin "2") (pinfunction "-IN_2") (pintype "input"))
      (node (ref "PHD83") (pin "3") (pinfunction "2_3") (pintype "bidirectional"))
      (node (ref "PHD83") (pin "4") (pinfunction "2_4") (pintype "bidirectional"))
      (node (ref "R2") (pin "1") (pinfunction "1_1") (pintype "passive"))
    )
    (net (code "187") (name "/PD84") (class "Default")
      (node (ref "IC3") (pin "6") (pinfunction "-IN_6") (pintype "input"))
      (node (ref "PHD84") (pin "3") (pinfunction "2_3") (pintype "bidirectional"))
      (node (ref "PHD84") (pin "4") (pinfunction "2_4") (pintype "bidirectional"))
      (node (ref "R17") (pin "1") (pinfunction "1_1") (pintype "passive"))
    )
    (net (code "188") (name "/PD85") (class "Default")
      (node (ref "IC9") (pin "2") (pinfunction "-IN_2") (pintype "input"))
      (node (ref "PHD85") (pin "3") (pinfunction "2_3") (pintype "bidirectional"))
      (node (ref "PHD85") (pin "4") (pinfunction "2_4") (pintype "bidirectional"))
      (node (ref "R10") (pin "1") (pinfunction "1_1") (pintype "passive"))
    )
    (net (code "189") (name "/PD86") (class "Default")
      (node (ref "IC9") (pin "6") (pinfunction "-IN_6") (pintype "input"))
      (node (ref "PHD86") (pin "3") (pinfunction "2_3") (pintype "bidirectional"))
      (node (ref "PHD86") (pin "4") (pinfunction "2_4") (pintype "bidirectional"))
      (node (ref "R21") (pin "1") (pinfunction "1_1") (pintype "passive"))
    )
    (net (code "190") (name "/PD87") (class "Default")
      (node (ref "IC21") (pin "2") (pinfunction "-IN_2") (pintype "input"))
      (node (ref "PHD87") (pin "3") (pinfunction "2_3") (pintype "bidirectional"))
      (node (ref "PHD87") (pin "4") (pinfunction "2_4") (pintype "bidirectional"))
      (node (ref "R73") (pin "1") (pinfunction "1_1") (pintype "passive"))
    )
    (net (code "191") (name "/PD88") (class "Default")
      (node (ref "IC21") (pin "6") (pinfunction "-IN_6") (pintype "input"))
      (node (ref "PHD88") (pin "3") (pinfunction "2_3") (pintype "bidirectional"))
      (node (ref "PHD88") (pin "4") (pinfunction "2_4") (pintype "bidirectional"))
      (node (ref "R81") (pin "1") (pinfunction "1_1") (pintype "passive"))
    )
    (net (code "192") (name "/PD89") (class "Default")
      (node (ref "IC22") (pin "13") (pinfunction "-IN_13") (pintype "input"))
      (node (ref "PHD89") (pin "3") (pinfunction "2_3") (pintype "bidirectional"))
      (node (ref "PHD89") (pin "4") (pinfunction "2_4") (pintype "bidirectional"))
      (node (ref "R93") (pin "1") (pinfunction "1_1") (pintype "passive"))
    )
    (net (code "193") (name "/PD90") (class "Default")
      (node (ref "IC22") (pin "9") (pinfunction "-IN_9") (pintype "input"))
      (node (ref "PHD90") (pin "3") (pinfunction "2_3") (pintype "bidirectional"))
      (node (ref "PHD90") (pin "4") (pinfunction "2_4") (pintype "bidirectional"))
      (node (ref "R88") (pin "1") (pinfunction "1_1") (pintype "passive"))
    )
    (net (code "194") (name "/PD91") (class "Default")
      (node (ref "IC3") (pin "13") (pinfunction "-IN_13") (pintype "input"))
      (node (ref "PHD91") (pin "3") (pinfunction "2_3") (pintype "bidirectional"))
      (node (ref "PHD91") (pin "4") (pinfunction "2_4") (pintype "bidirectional"))
      (node (ref "R45") (pin "1") (pinfunction "1_1") (pintype "passive"))
    )
    (net (code "195") (name "/PD92") (class "Default")
      (node (ref "IC3") (pin "9") (pinfunction "-IN_9") (pintype "input"))
      (node (ref "PHD92") (pin "3") (pinfunction "2_3") (pintype "bidirectional"))
      (node (ref "PHD92") (pin "4") (pinfunction "2_4") (pintype "bidirectional"))
      (node (ref "R34") (pin "1") (pinfunction "1_1") (pintype "passive"))
    )
    (net (code "196") (name "/PD93") (class "Default")
      (node (ref "IC9") (pin "13") (pinfunction "-IN_13") (pintype "input"))
      (node (ref "PHD93") (pin "3") (pinfunction "2_3") (pintype "bidirectional"))
      (node (ref "PHD93") (pin "4") (pinfunction "2_4") (pintype "bidirectional"))
      (node (ref "R37") (pin "1") (pinfunction "1_1") (pintype "passive"))
    )
    (net (code "197") (name "/PD94") (class "Default")
      (node (ref "IC9") (pin "9") (pinfunction "-IN_9") (pintype "input"))
      (node (ref "PHD94") (pin "3") (pinfunction "2_3") (pintype "bidirectional"))
      (node (ref "PHD94") (pin "4") (pinfunction "2_4") (pintype "bidirectional"))
      (node (ref "R28") (pin "1") (pinfunction "1_1") (pintype "passive"))
    )
    (net (code "198") (name "/PD95") (class "Default")
      (node (ref "IC21") (pin "13") (pinfunction "-IN_13") (pintype "input"))
      (node (ref "PHD95") (pin "3") (pinfunction "2_3") (pintype "bidirectional"))
      (node (ref "PHD95") (pin "4") (pinfunction "2_4") (pintype "bidirectional"))
      (node (ref "R97") (pin "1") (pinfunction "1_1") (pintype "passive"))
    )
    (net (code "199") (name "/PD96") (class "Default")
      (node (ref "IC21") (pin "9") (pinfunction "-IN_9") (pintype "input"))
      (node (ref "PHD96") (pin "3") (pinfunction "2_3") (pintype "bidirectional"))
      (node (ref "PHD96") (pin "4") (pinfunction "2_4") (pintype "bidirectional"))
      (node (ref "R89") (pin "1") (pinfunction "1_1") (pintype "passive"))
    )
    (net (code "200") (name "/S0") (class "Default")
      (node (ref "J2") (pin "1") (pinfunction "1_1") (pintype "passive"))
      (node (ref "U1") (pin "10") (pinfunction "SEL0_10") (pintype "bidirectional"))
      (node (ref "U2") (pin "10") (pinfunction "SEL0_10") (pintype "bidirectional"))
      (node (ref "U3") (pin "10") (pinfunction "SEL0_10") (pintype "bidirectional"))
      (node (ref "U4") (pin "10") (pinfunction "SEL0_10") (pintype "bidirectional"))
      (node (ref "U5") (pin "10") (pinfunction "SEL0_10") (pintype "bidirectional"))
      (node (ref "U6") (pin "10") (pinfunction "SEL0_10") (pintype "bidirectional"))
    )
    (net (code "201") (name "/S1") (class "Default")
      (node (ref "J2") (pin "2") (pinfunction "2_2") (pintype "passive"))
      (node (ref "U1") (pin "11") (pinfunction "SEL1_11") (pintype "bidirectional"))
      (node (ref "U2") (pin "11") (pinfunction "SEL1_11") (pintype "bidirectional"))
      (node (ref "U3") (pin "11") (pinfunction "SEL1_11") (pintype "bidirectional"))
      (node (ref "U4") (pin "11") (pinfunction "SEL1_11") (pintype "bidirectional"))
      (node (ref "U5") (pin "11") (pinfunction "SEL1_11") (pintype "bidirectional"))
      (node (ref "U6") (pin "11") (pinfunction "SEL1_11") (pintype "bidirectional"))
    )
    (net (code "202") (name "/S2") (class "Default")
      (node (ref "J2") (pin "3") (pinfunction "3_3") (pintype "passive"))
      (node (ref "U1") (pin "14") (pinfunction "SEL2_14") (pintype "bidirectional"))
      (node (ref "U2") (pin "14") (pinfunction "SEL2_14") (pintype "bidirectional"))
      (node (ref "U3") (pin "14") (pinfunction "SEL2_14") (pintype "bidirectional"))
      (node (ref "U4") (pin "14") (pinfunction "SEL2_14") (pintype "bidirectional"))
      (node (ref "U5") (pin "14") (pinfunction "SEL2_14") (pintype "bidirectional"))
      (node (ref "U6") (pin "14") (pinfunction "SEL2_14") (pintype "bidirectional"))
    )
    (net (code "203") (name "/S3") (class "Default")
      (node (ref "J2") (pin "4") (pinfunction "4_4") (pintype "passive"))
      (node (ref "U1") (pin "13") (pinfunction "SEL3_13") (pintype "bidirectional"))
      (node (ref "U2") (pin "13") (pinfunction "SEL3_13") (pintype "bidirectional"))
      (node (ref "U3") (pin "13") (pinfunction "SEL3_13") (pintype "bidirectional"))
      (node (ref "U4") (pin "13") (pinfunction "SEL3_13") (pintype "bidirectional"))
      (node (ref "U5") (pin "13") (pinfunction "SEL3_13") (pintype "bidirectional"))
      (node (ref "U6") (pin "13") (pinfunction "SEL3_13") (pintype "bidirectional"))
    )
    (net (code "204") (name "GND") (class "Default")
      (node (ref "C1") (pin "2") (pinfunction "2_2") (pintype "passive"))
      (node (ref "C10") (pin "2") (pinfunction "2_2") (pintype "passive"))
      (node (ref "C11") (pin "2") (pinfunction "2_2") (pintype "passive"))
      (node (ref "C12") (pin "2") (pinfunction "2_2") (pintype "passive"))
      (node (ref "C13") (pin "2") (pinfunction "2_2") (pintype "passive"))
      (node (ref "C14") (pin "2") (pinfunction "2_2") (pintype "passive"))
      (node (ref "C15") (pin "2") (pinfunction "2_2") (pintype "passive"))
      (node (ref "C16") (pin "2") (pinfunction "2_2") (pintype "passive"))
      (node (ref "C17") (pin "2") (pinfunction "2_2") (pintype "passive"))
      (node (ref "C18") (pin "2") (pinfunction "2_2") (pintype "passive"))
      (node (ref "C19") (pin "2") (pinfunction "2_2") (pintype "passive"))
      (node (ref "C2") (pin "2") (pinfunction "2_2") (pintype "passive"))
      (node (ref "C20") (pin "2") (pinfunction "2_2") (pintype "passive"))
      (node (ref "C21") (pin "2") (pinfunction "2_2") (pintype "passive"))
      (node (ref "C22") (pin "2") (pinfunction "2_2") (pintype "passive"))
      (node (ref "C23") (pin "2") (pinfunction "2_2") (pintype "passive"))
      (node (ref "C25") (pin "2") (pinfunction "2_2") (pintype "passive"))
      (node (ref "C3") (pin "2") (pinfunction "2_2") (pintype "passive"))
      (node (ref "C4") (pin "2") (pinfunction "2_2") (pintype "passive"))
      (node (ref "C5") (pin "2") (pinfunction "2_2") (pintype "passive"))
      (node (ref "C6") (pin "2") (pinfunction "2_2") (pintype "passive"))
      (node (ref "C7") (pin "2") (pinfunction "2_2") (pintype "passive"))
      (node (ref "C8") (pin "2") (pinfunction "2_2") (pintype "passive"))
      (node (ref "C9") (pin "2") (pinfunction "2_2") (pintype "passive"))
      (node (ref "IC1") (pin "10") (pinfunction "+IN_10") (pintype "input"))
      (node (ref "IC1") (pin "11") (pinfunction "V-_11") (pintype "power_in"))
      (node (ref "IC1") (pin "12") (pinfunction "+IN_12") (pintype "input"))
      (node (ref "IC1") (pin "3") (pinfunction "+IN_3") (pintype "input"))
      (node (ref "IC1") (pin "5") (pinfunction "+IN_5") (pintype "input"))
      (node (ref "IC10") (pin "10") (pinfunction "+IN_10") (pintype "input"))
      (node (ref "IC10") (pin "11") (pinfunction "V-_11") (pintype "power_in"))
      (node (ref "IC10") (pin "12") (pinfunction "+IN_12") (pintype "input"))
      (node (ref "IC10") (pin "3") (pinfunction "+IN_3") (pintype "input"))
      (node (ref "IC10") (pin "5") (pinfunction "+IN_5") (pintype "input"))
      (node (ref "IC11") (pin "10") (pinfunction "+IN_10") (pintype "input"))
      (node (ref "IC11") (pin "11") (pinfunction "V-_11") (pintype "power_in"))
      (node (ref "IC11") (pin "12") (pinfunction "+IN_12") (pintype "input"))
      (node (ref "IC11") (pin "3") (pinfunction "+IN_3") (pintype "input"))
      (node (ref "IC11") (pin "5") (pinfunction "+IN_5") (pintype "input"))
      (node (ref "IC12") (pin "10") (pinfunction "+IN_10") (pintype "input"))
      (node (ref "IC12") (pin "11") (pinfunction "V-_11") (pintype "power_in"))
      (node (ref "IC12") (pin "12") (pinfunction "+IN_12") (pintype "input"))
      (node (ref "IC12") (pin "3") (pinfunction "+IN_3") (pintype "input"))
      (node (ref "IC12") (pin "5") (pinfunction "+IN_5") (pintype "input"))
      (node (ref "IC13") (pin "10") (pinfunction "+IN_10") (pintype "input"))
      (node (ref "IC13") (pin "11") (pinfunction "V-_11") (pintype "power_in"))
      (node (ref "IC13") (pin "12") (pinfunction "+IN_12") (pintype "input"))
      (node (ref "IC13") (pin "3") (pinfunction "+IN_3") (pintype "input"))
      (node (ref "IC13") (pin "5") (pinfunction "+IN_5") (pintype "input"))
      (node (ref "IC14") (pin "10") (pinfunction "+IN_10") (pintype "input"))
      (node (ref "IC14") (pin "11") (pinfunction "V-_11") (pintype "power_in"))
      (node (ref "IC14") (pin "12") (pinfunction "+IN_12") (pintype "input"))
      (node (ref "IC14") (pin "3") (pinfunction "+IN_3") (pintype "input"))
      (node (ref "IC14") (pin "5") (pinfunction "+IN_5") (pintype "input"))
      (node (ref "IC15") (pin "10") (pinfunction "+IN_10") (pintype "input"))
      (node (ref "IC15") (pin "11") (pinfunction "V-_11") (pintype "power_in"))
      (node (ref "IC15") (pin "12") (pinfunction "+IN_12") (pintype "input"))
      (node (ref "IC15") (pin "3") (pinfunction "+IN_3") (pintype "input"))
      (node (ref "IC15") (pin "5") (pinfunction "+IN_5") (pintype "input"))
      (node (ref "IC16") (pin "10") (pinfunction "+IN_10") (pintype "input"))
      (node (ref "IC16") (pin "11") (pinfunction "V-_11") (pintype "power_in"))
      (node (ref "IC16") (pin "12") (pinfunction "+IN_12") (pintype "input"))
      (node (ref "IC16") (pin "3") (pinfunction "+IN_3") (pintype "input"))
      (node (ref "IC16") (pin "5") (pinfunction "+IN_5") (pintype "input"))
      (node (ref "IC17") (pin "10") (pinfunction "+IN_10") (pintype "input"))
      (node (ref "IC17") (pin "11") (pinfunction "V-_11") (pintype "power_in"))
      (node (ref "IC17") (pin "12") (pinfunction "+IN_12") (pintype "input"))
      (node (ref "IC17") (pin "3") (pinfunction "+IN_3") (pintype "input"))
      (node (ref "IC17") (pin "5") (pinfunction "+IN_5") (pintype "input"))
      (node (ref "IC18") (pin "10") (pinfunction "+IN_10") (pintype "input"))
      (node (ref "IC18") (pin "11") (pinfunction "V-_11") (pintype "power_in"))
      (node (ref "IC18") (pin "12") (pinfunction "+IN_12") (pintype "input"))
      (node (ref "IC18") (pin "3") (pinfunction "+IN_3") (pintype "input"))
      (node (ref "IC18") (pin "5") (pinfunction "+IN_5") (pintype "input"))
      (node (ref "IC19") (pin "10") (pinfunction "+IN_10") (pintype "input"))
      (node (ref "IC19") (pin "11") (pinfunction "V-_11") (pintype "power_in"))
      (node (ref "IC19") (pin "12") (pinfunction "+IN_12") (pintype "input"))
      (node (ref "IC19") (pin "3") (pinfunction "+IN_3") (pintype "input"))
      (node (ref "IC19") (pin "5") (pinfunction "+IN_5") (pintype "input"))
      (node (ref "IC2") (pin "10") (pinfunction "+IN_10") (pintype "input"))
      (node (ref "IC2") (pin "11") (pinfunction "V-_11") (pintype "power_in"))
      (node (ref "IC2") (pin "12") (pinfunction "+IN_12") (pintype "input"))
      (node (ref "IC2") (pin "3") (pinfunction "+IN_3") (pintype "input"))
      (node (ref "IC2") (pin "5") (pinfunction "+IN_5") (pintype "input"))
      (node (ref "IC20") (pin "10") (pinfunction "+IN_10") (pintype "input"))
      (node (ref "IC20") (pin "11") (pinfunction "V-_11") (pintype "power_in"))
      (node (ref "IC20") (pin "12") (pinfunction "+IN_12") (pintype "input"))
      (node (ref "IC20") (pin "3") (pinfunction "+IN_3") (pintype "input"))
      (node (ref "IC20") (pin "5") (pinfunction "+IN_5") (pintype "input"))
      (node (ref "IC21") (pin "10") (pinfunction "+IN_10") (pintype "input"))
      (node (ref "IC21") (pin "11") (pinfunction "V-_11") (pintype "power_in"))
      (node (ref "IC21") (pin "12") (pinfunction "+IN_12") (pintype "input"))
      (node (ref "IC21") (pin "3") (pinfunction "+IN_3") (pintype "input"))
      (node (ref "IC21") (pin "5") (pinfunction "+IN_5") (pintype "input"))
      (node (ref "IC22") (pin "10") (pinfunction "+IN_10") (pintype "input"))
      (node (ref "IC22") (pin "11") (pinfunction "V-_11") (pintype "power_in"))
      (node (ref "IC22") (pin "12") (pinfunction "+IN_12") (pintype "input"))
      (node (ref "IC22") (pin "3") (pinfunction "+IN_3") (pintype "input"))
      (node (ref "IC22") (pin "5") (pinfunction "+IN_5") (pintype "input"))
      (node (ref "IC23") (pin "10") (pinfunction "+IN_10") (pintype "input"))
      (node (ref "IC23") (pin "11") (pinfunction "V-_11") (pintype "power_in"))
      (node (ref "IC23") (pin "12") (pinfunction "+IN_12") (pintype "input"))
      (node (ref "IC23") (pin "3") (pinfunction "+IN_3") (pintype "input"))
      (node (ref "IC23") (pin "5") (pinfunction "+IN_5") (pintype "input"))
      (node (ref "IC24") (pin "10") (pinfunction "+IN_10") (pintype "input"))
      (node (ref "IC24") (pin "11") (pinfunction "V-_11") (pintype "power_in"))
      (node (ref "IC24") (pin "12") (pinfunction "+IN_12") (pintype "input"))
      (node (ref "IC24") (pin "3") (pinfunction "+IN_3") (pintype "input"))
      (node (ref "IC24") (pin "5") (pinfunction "+IN_5") (pintype "input"))
      (node (ref "IC3") (pin "10") (pinfunction "+IN_10") (pintype "input"))
      (node (ref "IC3") (pin "11") (pinfunction "V-_11") (pintype "power_in"))
      (node (ref "IC3") (pin "12") (pinfunction "+IN_12") (pintype "input"))
      (node (ref "IC3") (pin "3") (pinfunction "+IN_3") (pintype "input"))
      (node (ref "IC3") (pin "5") (pinfunction "+IN_5") (pintype "input"))
      (node (ref "IC4") (pin "10") (pinfunction "+IN_10") (pintype "input"))
      (node (ref "IC4") (pin "11") (pinfunction "V-_11") (pintype "power_in"))
      (node (ref "IC4") (pin "12") (pinfunction "+IN_12") (pintype "input"))
      (node (ref "IC4") (pin "3") (pinfunction "+IN_3") (pintype "input"))
      (node (ref "IC4") (pin "5") (pinfunction "+IN_5") (pintype "input"))
      (node (ref "IC5") (pin "10") (pinfunction "+IN_10") (pintype "input"))
      (node (ref "IC5") (pin "11") (pinfunction "V-_11") (pintype "power_in"))
      (node (ref "IC5") (pin "12") (pinfunction "+IN_12") (pintype "input"))
      (node (ref "IC5") (pin "3") (pinfunction "+IN_3") (pintype "input"))
      (node (ref "IC5") (pin "5") (pinfunction "+IN_5") (pintype "input"))
      (node (ref "IC6") (pin "10") (pinfunction "+IN_10") (pintype "input"))
      (node (ref "IC6") (pin "11") (pinfunction "V-_11") (pintype "power_in"))
      (node (ref "IC6") (pin "12") (pinfunction "+IN_12") (pintype "input"))
      (node (ref "IC6") (pin "3") (pinfunction "+IN_3") (pintype "input"))
      (node (ref "IC6") (pin "5") (pinfunction "+IN_5") (pintype "input"))
      (node (ref "IC7") (pin "10") (pinfunction "+IN_10") (pintype "input"))
      (node (ref "IC7") (pin "11") (pinfunction "V-_11") (pintype "power_in"))
      (node (ref "IC7") (pin "12") (pinfunction "+IN_12") (pintype "input"))
      (node (ref "IC7") (pin "3") (pinfunction "+IN_3") (pintype "input"))
      (node (ref "IC7") (pin "5") (pinfunction "+IN_5") (pintype "input"))
      (node (ref "IC8") (pin "10") (pinfunction "+IN_10") (pintype "input"))
      (node (ref "IC8") (pin "11") (pinfunction "V-_11") (pintype "power_in"))
      (node (ref "IC8") (pin "12") (pinfunction "+IN_12") (pintype "input"))
      (node (ref "IC8") (pin "3") (pinfunction "+IN_3") (pintype "input"))
      (node (ref "IC8") (pin "5") (pinfunction "+IN_5") (pintype "input"))
      (node (ref "IC9") (pin "10") (pinfunction "+IN_10") (pintype "input"))
      (node (ref "IC9") (pin "11") (pinfunction "V-_11") (pintype "power_in"))
      (node (ref "IC9") (pin "12") (pinfunction "+IN_12") (pintype "input"))
      (node (ref "IC9") (pin "3") (pinfunction "+IN_3") (pintype "input"))
      (node (ref "IC9") (pin "5") (pinfunction "+IN_5") (pintype "input"))
      (node (ref "J2") (pin "6") (pinfunction "6_6") (pintype "passive"))
      (node (ref "PHD1") (pin "1") (pinfunction "1_1") (pintype "bidirectional"))
      (node (ref "PHD1") (pin "2") (pinfunction "1_2") (pintype "bidirectional"))
      (node (ref "PHD10") (pin "1") (pinfunction "1_1") (pintype "bidirectional"))
      (node (ref "PHD10") (pin "2") (pinfunction "1_2") (pintype "bidirectional"))
      (node (ref "PHD11") (pin "1") (pinfunction "1_1") (pintype "bidirectional"))
      (node (ref "PHD11") (pin "2") (pinfunction "1_2") (pintype "bidirectional"))
      (node (ref "PHD12") (pin "1") (pinfunction "1_1") (pintype "bidirectional"))
      (node (ref "PHD12") (pin "2") (pinfunction "1_2") (pintype "bidirectional"))
      (node (ref "PHD13") (pin "1") (pinfunction "1_1") (pintype "bidirectional"))
      (node (ref "PHD13") (pin "2") (pinfunction "1_2") (pintype "bidirectional"))
      (node (ref "PHD14") (pin "1") (pinfunction "1_1") (pintype "bidirectional"))
      (node (ref "PHD14") (pin "2") (pinfunction "1_2") (pintype "bidirectional"))
      (node (ref "PHD15") (pin "1") (pinfunction "1_1") (pintype "bidirectional"))
      (node (ref "PHD15") (pin "2") (pinfunction "1_2") (pintype "bidirectional"))
      (node (ref "PHD16") (pin "1") (pinfunction "1_1") (pintype "bidirectional"))
      (node (ref "PHD16") (pin "2") (pinfunction "1_2") (pintype "bidirectional"))
      (node (ref "PHD17") (pin "1") (pinfunction "1_1") (pintype "bidirectional"))
      (node (ref "PHD17") (pin "2") (pinfunction "1_2") (pintype "bidirectional"))
      (node (ref "PHD18") (pin "1") (pinfunction "1_1") (pintype "bidirectional"))
      (node (ref "PHD18") (pin "2") (pinfunction "1_2") (pintype "bidirectional"))
      (node (ref "PHD19") (pin "1") (pinfunction "1_1") (pintype "bidirectional"))
      (node (ref "PHD19") (pin "2") (pinfunction "1_2") (pintype "bidirectional"))
      (node (ref "PHD2") (pin "1") (pinfunction "1_1") (pintype "bidirectional"))
      (node (ref "PHD2") (pin "2") (pinfunction "1_2") (pintype "bidirectional"))
      (node (ref "PHD20") (pin "1") (pinfunction "1_1") (pintype "bidirectional"))
      (node (ref "PHD20") (pin "2") (pinfunction "1_2") (pintype "bidirectional"))
      (node (ref "PHD21") (pin "1") (pinfunction "1_1") (pintype "bidirectional"))
      (node (ref "PHD21") (pin "2") (pinfunction "1_2") (pintype "bidirectional"))
      (node (ref "PHD22") (pin "1") (pinfunction "1_1") (pintype "bidirectional"))
      (node (ref "PHD22") (pin "2") (pinfunction "1_2") (pintype "bidirectional"))
      (node (ref "PHD23") (pin "1") (pinfunction "1_1") (pintype "bidirectional"))
      (node (ref "PHD23") (pin "2") (pinfunction "1_2") (pintype "bidirectional"))
      (node (ref "PHD24") (pin "1") (pinfunction "1_1") (pintype "bidirectional"))
      (node (ref "PHD24") (pin "2") (pinfunction "1_2") (pintype "bidirectional"))
      (node (ref "PHD25") (pin "1") (pinfunction "1_1") (pintype "bidirectional"))
      (node (ref "PHD25") (pin "2") (pinfunction "1_2") (pintype "bidirectional"))
      (node (ref "PHD26") (pin "1") (pinfunction "1_1") (pintype "bidirectional"))
      (node (ref "PHD26") (pin "2") (pinfunction "1_2") (pintype "bidirectional"))
      (node (ref "PHD27") (pin "1") (pinfunction "1_1") (pintype "bidirectional"))
      (node (ref "PHD27") (pin "2") (pinfunction "1_2") (pintype "bidirectional"))
      (node (ref "PHD28") (pin "1") (pinfunction "1_1") (pintype "bidirectional"))
      (node (ref "PHD28") (pin "2") (pinfunction "1_2") (pintype "bidirectional"))
      (node (ref "PHD29") (pin "1") (pinfunction "1_1") (pintype "bidirectional"))
      (node (ref "PHD29") (pin "2") (pinfunction "1_2") (pintype "bidirectional"))
      (node (ref "PHD3") (pin "1") (pinfunction "1_1") (pintype "bidirectional"))
      (node (ref "PHD3") (pin "2") (pinfunction "1_2") (pintype "bidirectional"))
      (node (ref "PHD30") (pin "1") (pinfunction "1_1") (pintype "bidirectional"))
      (node (ref "PHD30") (pin "2") (pinfunction "1_2") (pintype "bidirectional"))
      (node (ref "PHD31") (pin "1") (pinfunction "1_1") (pintype "bidirectional"))
      (node (ref "PHD31") (pin "2") (pinfunction "1_2") (pintype "bidirectional"))
      (node (ref "PHD32") (pin "1") (pinfunction "1_1") (pintype "bidirectional"))
      (node (ref "PHD32") (pin "2") (pinfunction "1_2") (pintype "bidirectional"))
      (node (ref "PHD33") (pin "1") (pinfunction "1_1") (pintype "bidirectional"))
      (node (ref "PHD33") (pin "2") (pinfunction "1_2") (pintype "bidirectional"))
      (node (ref "PHD34") (pin "1") (pinfunction "1_1") (pintype "bidirectional"))
      (node (ref "PHD34") (pin "2") (pinfunction "1_2") (pintype "bidirectional"))
      (node (ref "PHD35") (pin "1") (pinfunction "1_1") (pintype "bidirectional"))
      (node (ref "PHD35") (pin "2") (pinfunction "1_2") (pintype "bidirectional"))
      (node (ref "PHD36") (pin "1") (pinfunction "1_1") (pintype "bidirectional"))
      (node (ref "PHD36") (pin "2") (pinfunction "1_2") (pintype "bidirectional"))
      (node (ref "PHD37") (pin "1") (pinfunction "1_1") (pintype "bidirectional"))
      (node (ref "PHD37") (pin "2") (pinfunction "1_2") (pintype "bidirectional"))
      (node (ref "PHD38") (pin "1") (pinfunction "1_1") (pintype "bidirectional"))
      (node (ref "PHD38") (pin "2") (pinfunction "1_2") (pintype "bidirectional"))
      (node (ref "PHD39") (pin "1") (pinfunction "1_1") (pintype "bidirectional"))
      (node (ref "PHD39") (pin "2") (pinfunction "1_2") (pintype "bidirectional"))
      (node (ref "PHD4") (pin "1") (pinfunction "1_1") (pintype "bidirectional"))
      (node (ref "PHD4") (pin "2") (pinfunction "1_2") (pintype "bidirectional"))
      (node (ref "PHD40") (pin "1") (pinfunction "1_1") (pintype "bidirectional"))
      (node (ref "PHD40") (pin "2") (pinfunction "1_2") (pintype "bidirectional"))
      (node (ref "PHD41") (pin "1") (pinfunction "1_1") (pintype "bidirectional"))
      (node (ref "PHD41") (pin "2") (pinfunction "1_2") (pintype "bidirectional"))
      (node (ref "PHD42") (pin "1") (pinfunction "1_1") (pintype "bidirectional"))
      (node (ref "PHD42") (pin "2") (pinfunction "1_2") (pintype "bidirectional"))
      (node (ref "PHD43") (pin "1") (pinfunction "1_1") (pintype "bidirectional"))
      (node (ref "PHD43") (pin "2") (pinfunction "1_2") (pintype "bidirectional"))
      (node (ref "PHD44") (pin "1") (pinfunction "1_1") (pintype "bidirectional"))
      (node (ref "PHD44") (pin "2") (pinfunction "1_2") (pintype "bidirectional"))
      (node (ref "PHD45") (pin "1") (pinfunction "1_1") (pintype "bidirectional"))
      (node (ref "PHD45") (pin "2") (pinfunction "1_2") (pintype "bidirectional"))
      (node (ref "PHD46") (pin "1") (pinfunction "1_1") (pintype "bidirectional"))
      (node (ref "PHD46") (pin "2") (pinfunction "1_2") (pintype "bidirectional"))
      (node (ref "PHD47") (pin "1") (pinfunction "1_1") (pintype "bidirectional"))
      (node (ref "PHD47") (pin "2") (pinfunction "1_2") (pintype "bidirectional"))
      (node (ref "PHD48") (pin "1") (pinfunction "1_1") (pintype "bidirectional"))
      (node (ref "PHD48") (pin "2") (pinfunction "1_2") (pintype "bidirectional"))
      (node (ref "PHD49") (pin "1") (pinfunction "1_1") (pintype "bidirectional"))
      (node (ref "PHD49") (pin "2") (pinfunction "1_2") (pintype "bidirectional"))
      (node (ref "PHD5") (pin "1") (pinfunction "1_1") (pintype "bidirectional"))
      (node (ref "PHD5") (pin "2") (pinfunction "1_2") (pintype "bidirectional"))
      (node (ref "PHD50") (pin "1") (pinfunction "1_1") (pintype "bidirectional"))
      (node (ref "PHD50") (pin "2") (pinfunction "1_2") (pintype "bidirectional"))
      (node (ref "PHD51") (pin "1") (pinfunction "1_1") (pintype "bidirectional"))
      (node (ref "PHD51") (pin "2") (pinfunction "1_2") (pintype "bidirectional"))
      (node (ref "PHD52") (pin "1") (pinfunction "1_1") (pintype "bidirectional"))
      (node (ref "PHD52") (pin "2") (pinfunction "1_2") (pintype "bidirectional"))
      (node (ref "PHD53") (pin "1") (pinfunction "1_1") (pintype "bidirectional"))
      (node (ref "PHD53") (pin "2") (pinfunction "1_2") (pintype "bidirectional"))
      (node (ref "PHD54") (pin "1") (pinfunction "1_1") (pintype "bidirectional"))
      (node (ref "PHD54") (pin "2") (pinfunction "1_2") (pintype "bidirectional"))
      (node (ref "PHD55") (pin "1") (pinfunction "1_1") (pintype "bidirectional"))
      (node (ref "PHD55") (pin "2") (pinfunction "1_2") (pintype "bidirectional"))
      (node (ref "PHD56") (pin "1") (pinfunction "1_1") (pintype "bidirectional"))
      (node (ref "PHD56") (pin "2") (pinfunction "1_2") (pintype "bidirectional"))
      (node (ref "PHD57") (pin "1") (pinfunction "1_1") (pintype "bidirectional"))
      (node (ref "PHD57") (pin "2") (pinfunction "1_2") (pintype "bidirectional"))
      (node (ref "PHD58") (pin "1") (pinfunction "1_1") (pintype "bidirectional"))
      (node (ref "PHD58") (pin "2") (pinfunction "1_2") (pintype "bidirectional"))
      (node (ref "PHD59") (pin "1") (pinfunction "1_1") (pintype "bidirectional"))
      (node (ref "PHD59") (pin "2") (pinfunction "1_2") (pintype "bidirectional"))
      (node (ref "PHD6") (pin "1") (pinfunction "1_1") (pintype "bidirectional"))
      (node (ref "PHD6") (pin "2") (pinfunction "1_2") (pintype "bidirectional"))
      (node (ref "PHD60") (pin "1") (pinfunction "1_1") (pintype "bidirectional"))
      (node (ref "PHD60") (pin "2") (pinfunction "1_2") (pintype "bidirectional"))
      (node (ref "PHD61") (pin "1") (pinfunction "1_1") (pintype "bidirectional"))
      (node (ref "PHD61") (pin "2") (pinfunction "1_2") (pintype "bidirectional"))
      (node (ref "PHD62") (pin "1") (pinfunction "1_1") (pintype "bidirectional"))
      (node (ref "PHD62") (pin "2") (pinfunction "1_2") (pintype "bidirectional"))
      (node (ref "PHD63") (pin "1") (pinfunction "1_1") (pintype "bidirectional"))
      (node (ref "PHD63") (pin "2") (pinfunction "1_2") (pintype "bidirectional"))
      (node (ref "PHD64") (pin "1") (pinfunction "1_1") (pintype "bidirectional"))
      (node (ref "PHD64") (pin "2") (pinfunction "1_2") (pintype "bidirectional"))
      (node (ref "PHD65") (pin "1") (pinfunction "1_1") (pintype "bidirectional"))
      (node (ref "PHD65") (pin "2") (pinfunction "1_2") (pintype "bidirectional"))
      (node (ref "PHD66") (pin "1") (pinfunction "1_1") (pintype "bidirectional"))
      (node (ref "PHD66") (pin "2") (pinfunction "1_2") (pintype "bidirectional"))
      (node (ref "PHD67") (pin "1") (pinfunction "1_1") (pintype "bidirectional"))
      (node (ref "PHD67") (pin "2") (pinfunction "1_2") (pintype "bidirectional"))
      (node (ref "PHD68") (pin "1") (pinfunction "1_1") (pintype "bidirectional"))
      (node (ref "PHD68") (pin "2") (pinfunction "1_2") (pintype "bidirectional"))
      (node (ref "PHD69") (pin "1") (pinfunction "1_1") (pintype "bidirectional"))
      (node (ref "PHD69") (pin "2") (pinfunction "1_2") (pintype "bidirectional"))
      (node (ref "PHD7") (pin "1") (pinfunction "1_1") (pintype "bidirectional"))
      (node (ref "PHD7") (pin "2") (pinfunction "1_2") (pintype "bidirectional"))
      (node (ref "PHD70") (pin "1") (pinfunction "1_1") (pintype "bidirectional"))
      (node (ref "PHD70") (pin "2") (pinfunction "1_2") (pintype "bidirectional"))
      (node (ref "PHD71") (pin "1") (pinfunction "1_1") (pintype "bidirectional"))
      (node (ref "PHD71") (pin "2") (pinfunction "1_2") (pintype "bidirectional"))
      (node (ref "PHD72") (pin "1") (pinfunction "1_1") (pintype "bidirectional"))
      (node (ref "PHD72") (pin "2") (pinfunction "1_2") (pintype "bidirectional"))
      (node (ref "PHD73") (pin "1") (pinfunction "1_1") (pintype "bidirectional"))
      (node (ref "PHD73") (pin "2") (pinfunction "1_2") (pintype "bidirectional"))
      (node (ref "PHD74") (pin "1") (pinfunction "1_1") (pintype "bidirectional"))
      (node (ref "PHD74") (pin "2") (pinfunction "1_2") (pintype "bidirectional"))
      (node (ref "PHD75") (pin "1") (pinfunction "1_1") (pintype "bidirectional"))
      (node (ref "PHD75") (pin "2") (pinfunction "1_2") (pintype "bidirectional"))
      (node (ref "PHD76") (pin "1") (pinfunction "1_1") (pintype "bidirectional"))
      (node (ref "PHD76") (pin "2") (pinfunction "1_2") (pintype "bidirectional"))
      (node (ref "PHD77") (pin "1") (pinfunction "1_1") (pintype "bidirectional"))
      (node (ref "PHD77") (pin "2") (pinfunction "1_2") (pintype "bidirectional"))
      (node (ref "PHD78") (pin "1") (pinfunction "1_1") (pintype "bidirectional"))
      (node (ref "PHD78") (pin "2") (pinfunction "1_2") (pintype "bidirectional"))
      (node (ref "PHD79") (pin "1") (pinfunction "1_1") (pintype "bidirectional"))
      (node (ref "PHD79") (pin "2") (pinfunction "1_2") (pintype "bidirectional"))
      (node (ref "PHD8") (pin "1") (pinfunction "1_1") (pintype "bidirectional"))
      (node (ref "PHD8") (pin "2") (pinfunction "1_2") (pintype "bidirectional"))
      (node (ref "PHD80") (pin "1") (pinfunction "1_1") (pintype "bidirectional"))
      (node (ref "PHD80") (pin "2") (pinfunction "1_2") (pintype "bidirectional"))
      (node (ref "PHD81") (pin "1") (pinfunction "1_1") (pintype "bidirectional"))
      (node (ref "PHD81") (pin "2") (pinfunction "1_2") (pintype "bidirectional"))
      (node (ref "PHD82") (pin "1") (pinfunction "1_1") (pintype "bidirectional"))
      (node (ref "PHD82") (pin "2") (pinfunction "1_2") (pintype "bidirectional"))
      (node (ref "PHD83") (pin "1") (pinfunction "1_1") (pintype "bidirectional"))
      (node (ref "PHD83") (pin "2") (pinfunction "1_2") (pintype "bidirectional"))
      (node (ref "PHD84") (pin "1") (pinfunction "1_1") (pintype "bidirectional"))
      (node (ref "PHD84") (pin "2") (pinfunction "1_2") (pintype "bidirectional"))
      (node (ref "PHD85") (pin "1") (pinfunction "1_1") (pintype "bidirectional"))
      (node (ref "PHD85") (pin "2") (pinfunction "1_2") (pintype "bidirectional"))
      (node (ref "PHD86") (pin "1") (pinfunction "1_1") (pintype "bidirectional"))
      (node (ref "PHD86") (pin "2") (pinfunction "1_2") (pintype "bidirectional"))
      (node (ref "PHD87") (pin "1") (pinfunction "1_1") (pintype "bidirectional"))
      (node (ref "PHD87") (pin "2") (pinfunction "1_2") (pintype "bidirectional"))
      (node (ref "PHD88") (pin "1") (pinfunction "1_1") (pintype "bidirectional"))
      (node (ref "PHD88") (pin "2") (pinfunction "1_2") (pintype "bidirectional"))
      (node (ref "PHD89") (pin "1") (pinfunction "1_1") (pintype "bidirectional"))
      (node (ref "PHD89") (pin "2") (pinfunction "1_2") (pintype "bidirectional"))
      (node (ref "PHD9") (pin "1") (pinfunction "1_1") (pintype "bidirectional"))
      (node (ref "PHD9") (pin "2") (pinfunction "1_2") (pintype "bidirectional"))
      (node (ref "PHD90") (pin "1") (pinfunction "1_1") (pintype "bidirectional"))
      (node (ref "PHD90") (pin "2") (pinfunction "1_2") (pintype "bidirectional"))
      (node (ref "PHD91") (pin "1") (pinfunction "1_1") (pintype "bidirectional"))
      (node (ref "PHD91") (pin "2") (pinfunction "1_2") (pintype "bidirectional"))
      (node (ref "PHD92") (pin "1") (pinfunction "1_1") (pintype "bidirectional"))
      (node (ref "PHD92") (pin "2") (pinfunction "1_2") (pintype "bidirectional"))
      (node (ref "PHD93") (pin "1") (pinfunction "1_1") (pintype "bidirectional"))
      (node (ref "PHD93") (pin "2") (pinfunction "1_2") (pintype "bidirectional"))
      (node (ref "PHD94") (pin "1") (pinfunction "1_1") (pintype "bidirectional"))
      (node (ref "PHD94") (pin "2") (pinfunction "1_2") (pintype "bidirectional"))
      (node (ref "PHD95") (pin "1") (pinfunction "1_1") (pintype "bidirectional"))
      (node (ref "PHD95") (pin "2") (pinfunction "1_2") (pintype "bidirectional"))
      (node (ref "PHD96") (pin "1") (pinfunction "1_1") (pintype "bidirectional"))
      (node (ref "PHD96") (pin "2") (pinfunction "1_2") (pintype "bidirectional"))
      (node (ref "U1") (pin "12") (pinfunction "GND_12") (pintype "bidirectional"))
      (node (ref "U1") (pin "15") (pinfunction "EN_15") (pintype "bidirectional"))
      (node (ref "U2") (pin "12") (pinfunction "GND_12") (pintype "bidirectional"))
      (node (ref "U2") (pin "15") (pinfunction "EN_15") (pintype "bidirectional"))
      (node (ref "U3") (pin "12") (pinfunction "GND_12") (pintype "bidirectional"))
      (node (ref "U3") (pin "15") (pinfunction "EN_15") (pintype "bidirectional"))
      (node (ref "U4") (pin "12") (pinfunction "GND_12") (pintype "bidirectional"))
      (node (ref "U4") (pin "15") (pinfunction "EN_15") (pintype "bidirectional"))
      (node (ref "U5") (pin "12") (pinfunction "GND_12") (pintype "bidirectional"))
      (node (ref "U5") (pin "15") (pinfunction "EN_15") (pintype "bidirectional"))
      (node (ref "U6") (pin "12") (pinfunction "GND_12") (pintype "bidirectional"))
      (node (ref "U6") (pin "15") (pinfunction "EN_15") (pintype "bidirectional"))
    )
  )
)
